# ARM_board.net
KiCad netlist of a schematic drawn in EAGLE
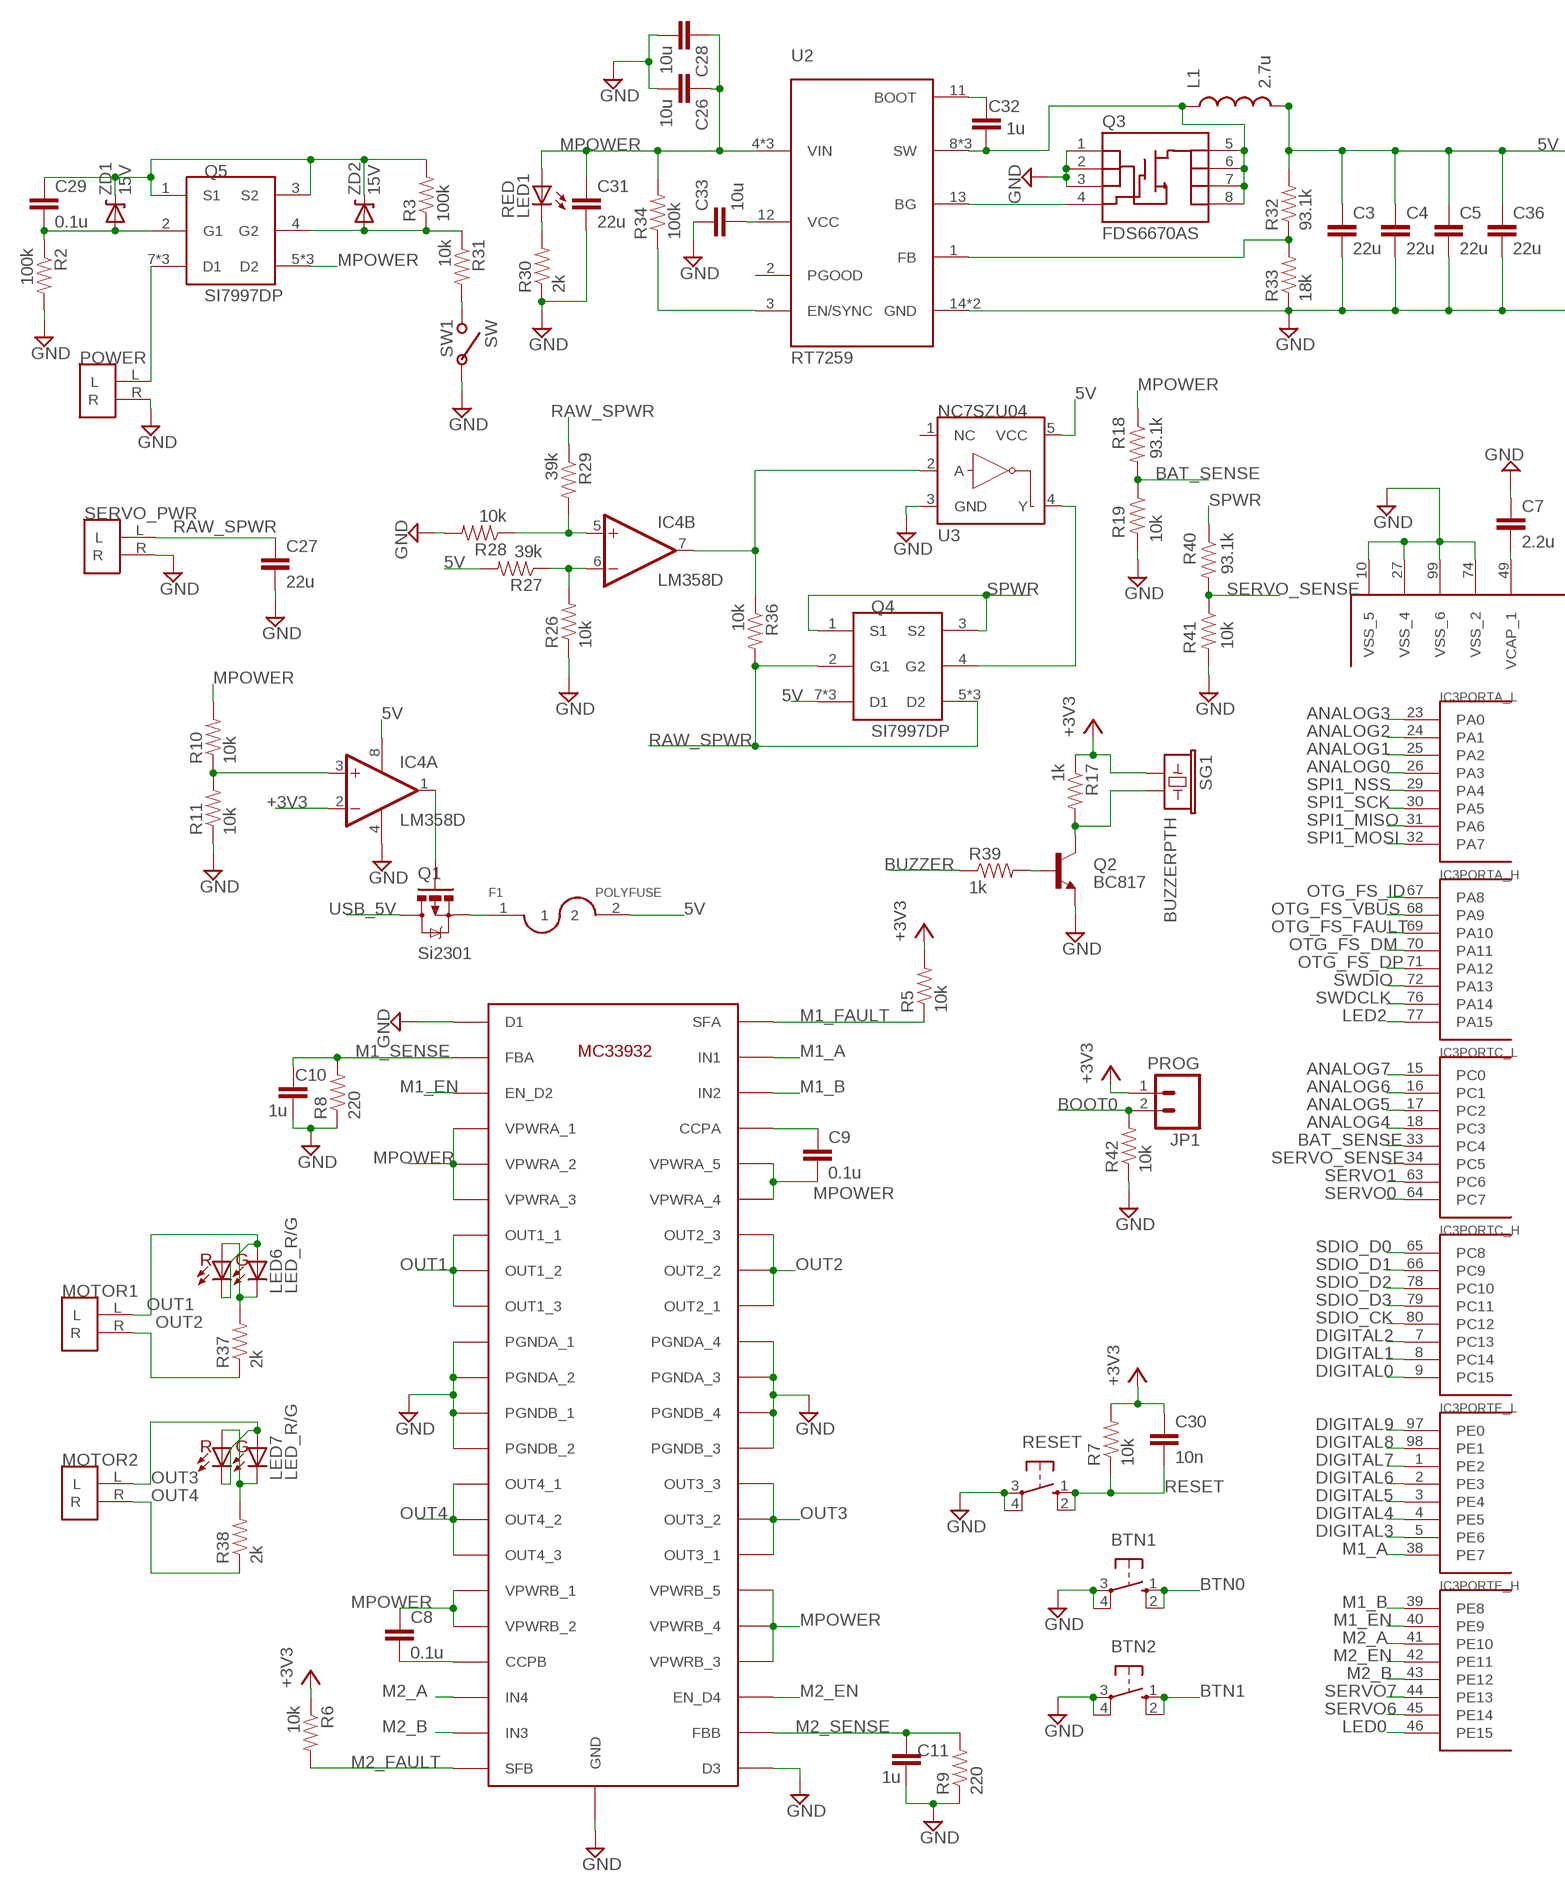
[diagram p0: schematic, sheet 1, part 1 of 2]
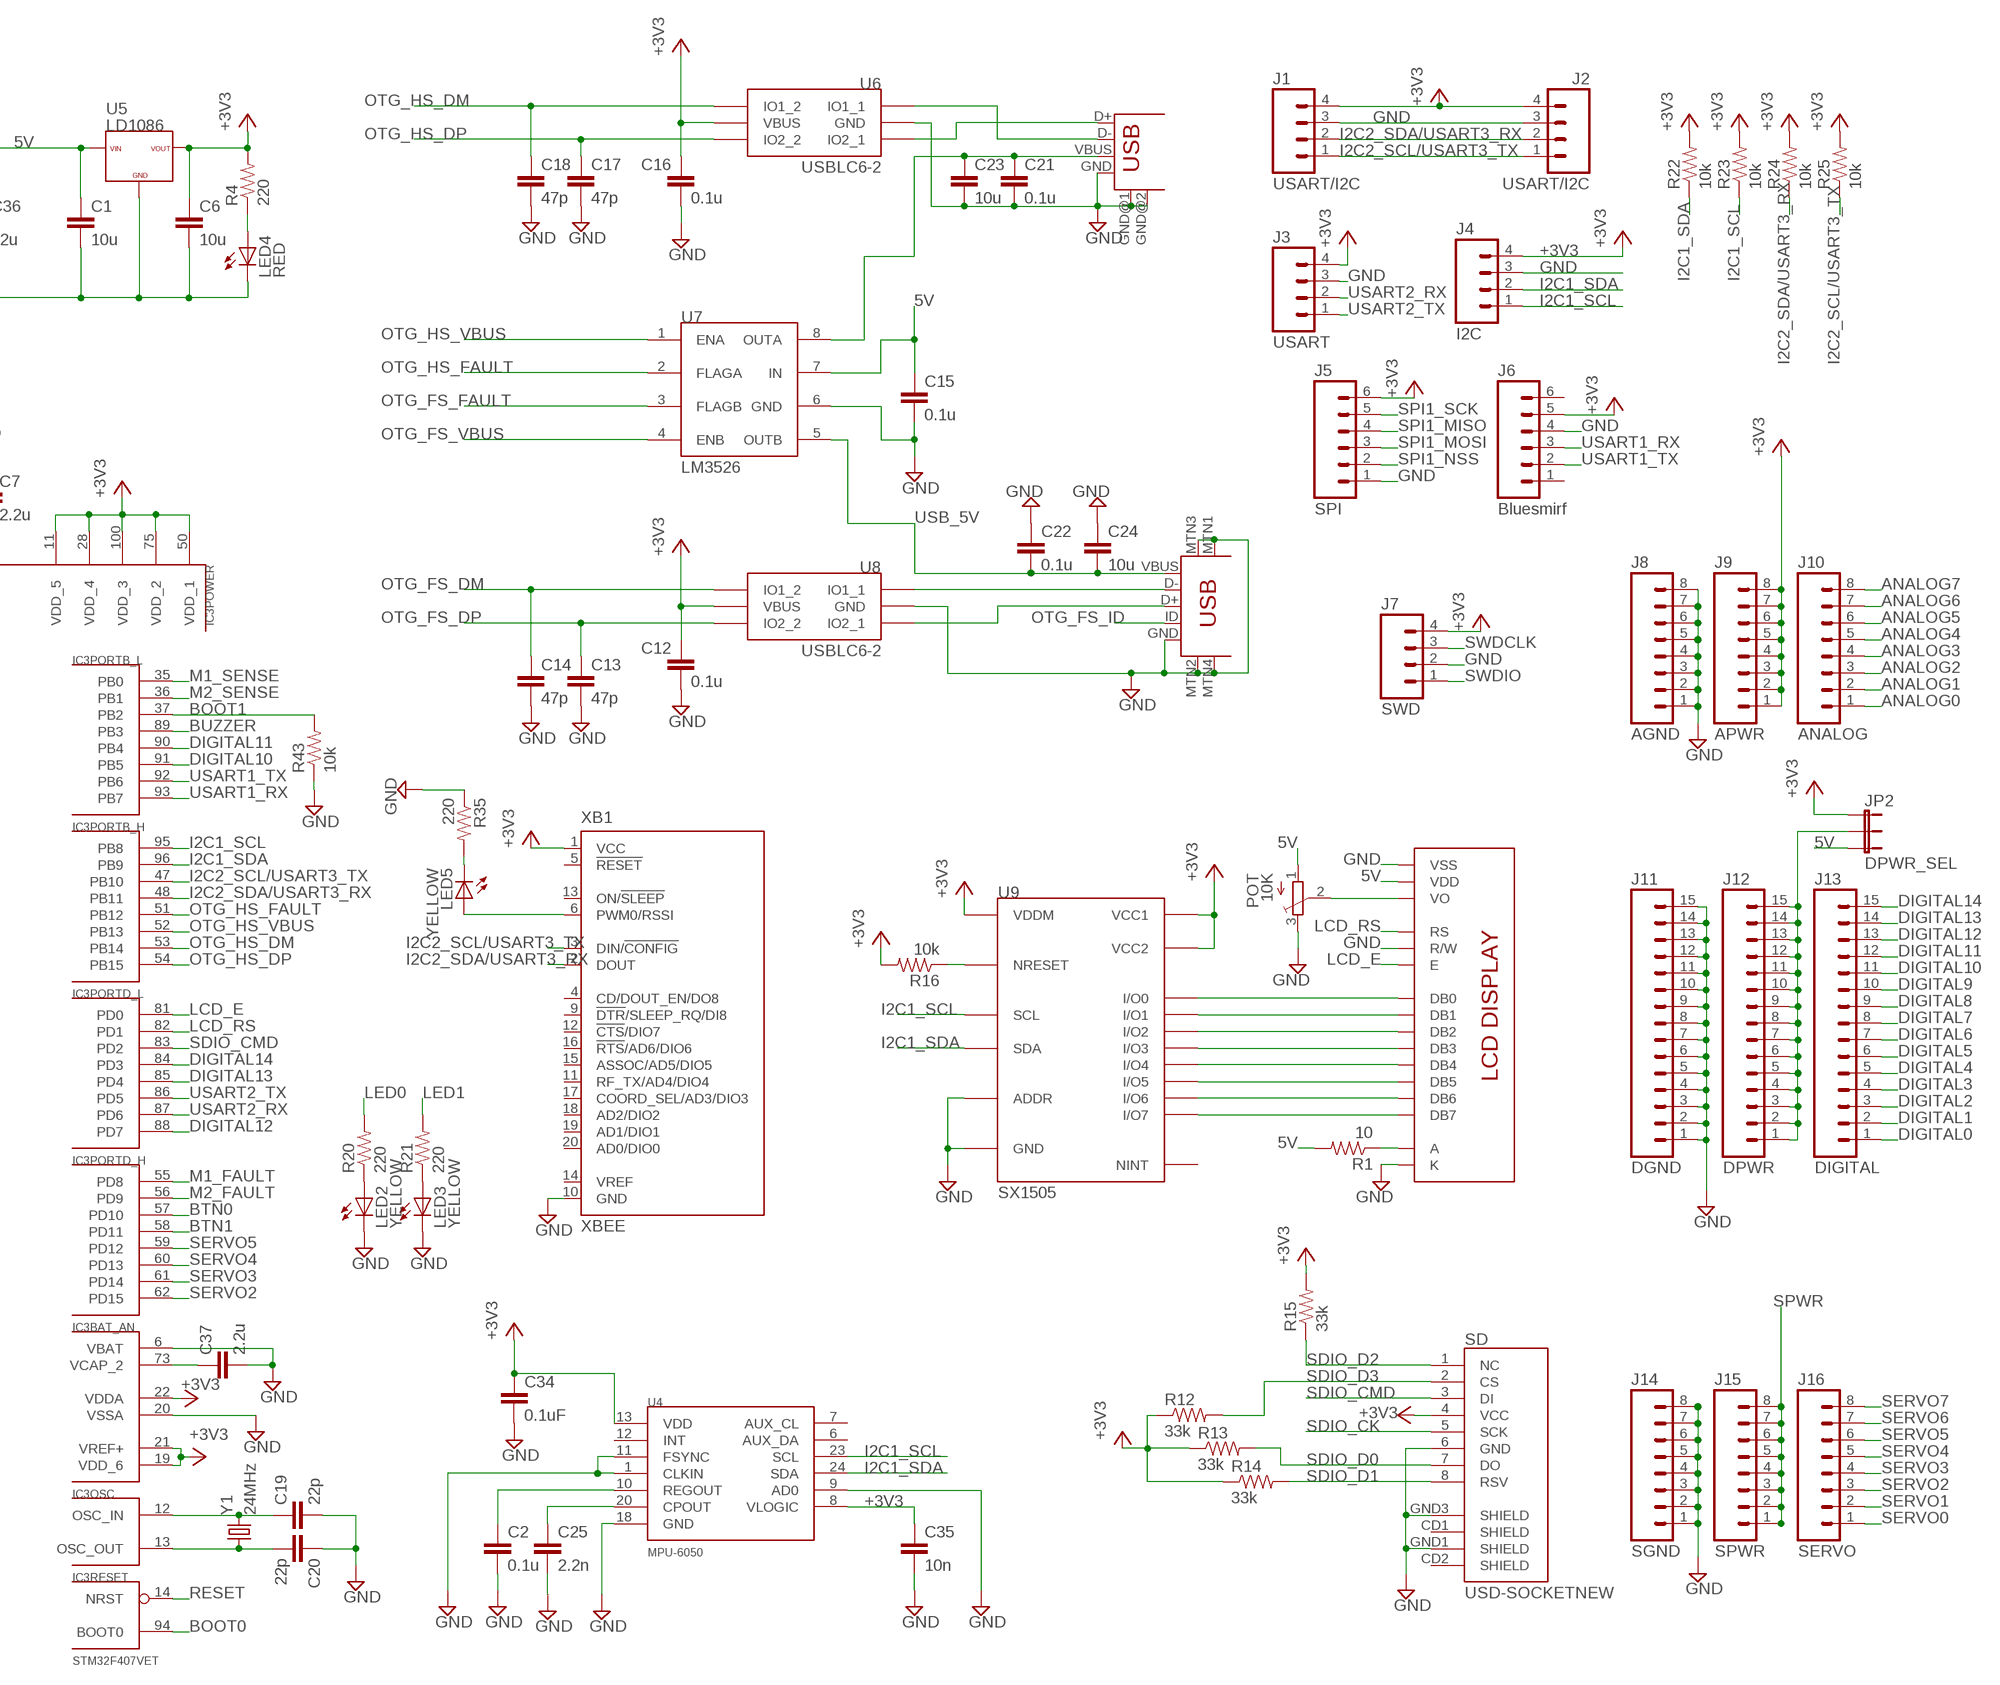
[diagram p1: schematic, sheet 1, part 2 of 2]

(export (version "E")
  (design (tool "Eeschema 10.0.6"))
  (components
    (comp (ref "BTN1")
      (value "10-XX")
      (footprint "eagle-import:B3F-10XX")
      (fields (field (name "MPN") "B3F-1000"))
      (libsource (lib "eagle-import") (part "10-XX"))
    )
    (comp (ref "BTN2")
      (value "10-XX")
      (footprint "eagle-import:B3F-10XX")
      (fields (field (name "MPN") "B3F-1000"))
      (libsource (lib "eagle-import") (part "10-XX"))
    )
    (comp (ref "C1")
      (value "10u")
      (footprint "eagle-import:0805")
      (libsource (lib "eagle-import") (part "CAP0805"))
    )
    (comp (ref "C2")
      (value "0.1u")
      (footprint "eagle-import:0603-CAP")
      (libsource (lib "eagle-import") (part "CAP0603-CAP"))
    )
    (comp (ref "C3")
      (value "22u")
      (footprint "eagle-import:0805")
      (libsource (lib "eagle-import") (part "CAP0805"))
    )
    (comp (ref "C4")
      (value "22u")
      (footprint "eagle-import:0805")
      (libsource (lib "eagle-import") (part "CAP0805"))
    )
    (comp (ref "C5")
      (value "22u")
      (footprint "eagle-import:0805")
      (libsource (lib "eagle-import") (part "CAP0805"))
    )
    (comp (ref "C6")
      (value "10u")
      (footprint "eagle-import:0805")
      (libsource (lib "eagle-import") (part "CAP0805"))
    )
    (comp (ref "C7")
      (value "2.2u")
      (footprint "eagle-import:0603-CAP")
      (libsource (lib "eagle-import") (part "CAP0603-CAP"))
    )
    (comp (ref "C8")
      (value "0.1u")
      (footprint "eagle-import:0603-CAP")
      (libsource (lib "eagle-import") (part "CAP0603-CAP"))
    )
    (comp (ref "C9")
      (value "0.1u")
      (footprint "eagle-import:0603-CAP")
      (libsource (lib "eagle-import") (part "CAP0603-CAP"))
    )
    (comp (ref "C10")
      (value "1u")
      (footprint "eagle-import:0603-CAP")
      (libsource (lib "eagle-import") (part "CAP0603-CAP"))
    )
    (comp (ref "C11")
      (value "1u")
      (footprint "eagle-import:0603-CAP")
      (libsource (lib "eagle-import") (part "CAP0603-CAP"))
    )
    (comp (ref "C12")
      (value "0.1u")
      (footprint "eagle-import:0603-CAP")
      (libsource (lib "eagle-import") (part "CAP0603-CAP"))
    )
    (comp (ref "C13")
      (value "47p")
      (footprint "eagle-import:0603-CAP")
      (libsource (lib "eagle-import") (part "CAP0603-CAP"))
    )
    (comp (ref "C14")
      (value "47p")
      (footprint "eagle-import:0603-CAP")
      (libsource (lib "eagle-import") (part "CAP0603-CAP"))
    )
    (comp (ref "C15")
      (value "0.1u")
      (footprint "eagle-import:0603-CAP")
      (libsource (lib "eagle-import") (part "CAP0603-CAP"))
    )
    (comp (ref "C16")
      (value "0.1u")
      (footprint "eagle-import:0603-CAP")
      (libsource (lib "eagle-import") (part "CAP0603-CAP"))
    )
    (comp (ref "C17")
      (value "47p")
      (footprint "eagle-import:0603-CAP")
      (libsource (lib "eagle-import") (part "CAP0603-CAP"))
    )
    (comp (ref "C18")
      (value "47p")
      (footprint "eagle-import:0603-CAP")
      (libsource (lib "eagle-import") (part "CAP0603-CAP"))
    )
    (comp (ref "C19")
      (value "22p")
      (footprint "eagle-import:0603-CAP")
      (libsource (lib "eagle-import") (part "CAP0603-CAP"))
    )
    (comp (ref "C20")
      (value "22p")
      (footprint "eagle-import:0603-CAP")
      (libsource (lib "eagle-import") (part "CAP0603-CAP"))
    )
    (comp (ref "C21")
      (value "0.1u")
      (footprint "eagle-import:0603-CAP")
      (libsource (lib "eagle-import") (part "CAP0603-CAP"))
    )
    (comp (ref "C22")
      (value "0.1u")
      (footprint "eagle-import:0603-CAP")
      (libsource (lib "eagle-import") (part "CAP0603-CAP"))
    )
    (comp (ref "C23")
      (value "10u")
      (footprint "eagle-import:0805")
      (libsource (lib "eagle-import") (part "CAP0805"))
    )
    (comp (ref "C24")
      (value "10u")
      (footprint "eagle-import:0805")
      (libsource (lib "eagle-import") (part "CAP0805"))
    )
    (comp (ref "C25")
      (value "2.2n")
      (footprint "eagle-import:0603-CAP")
      (libsource (lib "eagle-import") (part "CAP0603-CAP"))
    )
    (comp (ref "C26")
      (value "10u")
      (footprint "eagle-import:1206")
      (libsource (lib "eagle-import") (part "CAP1206"))
    )
    (comp (ref "C27")
      (value "22u")
      (footprint "eagle-import:1206")
      (libsource (lib "eagle-import") (part "CAP1206"))
    )
    (comp (ref "C28")
      (value "10u")
      (footprint "eagle-import:1206")
      (libsource (lib "eagle-import") (part "CAP1206"))
    )
    (comp (ref "C29")
      (value "0.1u")
      (footprint "eagle-import:0603-CAP")
      (libsource (lib "eagle-import") (part "CAP0603-CAP"))
    )
    (comp (ref "C30")
      (value "10n")
      (footprint "eagle-import:0603-CAP")
      (libsource (lib "eagle-import") (part "CAP0603-CAP"))
    )
    (comp (ref "C31")
      (value "22u")
      (footprint "eagle-import:1206")
      (libsource (lib "eagle-import") (part "CAP1206"))
    )
    (comp (ref "C32")
      (value "1u")
      (footprint "eagle-import:0603-CAP")
      (libsource (lib "eagle-import") (part "CAP0603-CAP"))
    )
    (comp (ref "C33")
      (value "10u")
      (footprint "eagle-import:0805")
      (libsource (lib "eagle-import") (part "CAP0805"))
    )
    (comp (ref "C34")
      (value "0.1uF")
      (footprint "eagle-import:0603-CAP")
      (libsource (lib "eagle-import") (part "CAP0603-CAP"))
    )
    (comp (ref "C35")
      (value "10n")
      (footprint "eagle-import:0603-CAP")
      (libsource (lib "eagle-import") (part "CAP0603-CAP"))
    )
    (comp (ref "C36")
      (value "22u")
      (footprint "eagle-import:0805")
      (libsource (lib "eagle-import") (part "CAP0805"))
    )
    (comp (ref "C37")
      (value "2.2u")
      (footprint "eagle-import:0603-CAP")
      (libsource (lib "eagle-import") (part "CAP0603-CAP"))
    )
    (comp (ref "F1")
      (value "POLYFUSE")
      (footprint "eagle-import:1206")
      (libsource (lib "eagle-import") (part "POLYFUSE"))
    )
    (comp (ref "IC3")
      (value "STM32F407VET")
      (footprint "eagle-import:TQFP100")
      (libsource (lib "eagle-import") (part "STM32F407VET"))
    )
    (comp (ref "IC4")
      (value "LM358D")
      (footprint "eagle-import:SO08")
      (libsource (lib "eagle-import") (part "LM358D"))
    )
    (comp (ref "J1")
      (value "USART/I2C")
      (footprint "eagle-import:1X04")
      (libsource (lib "eagle-import") (part "M04PTH"))
    )
    (comp (ref "J2")
      (value "USART/I2C")
      (footprint "eagle-import:1X04")
      (libsource (lib "eagle-import") (part "M04PTH"))
    )
    (comp (ref "J3")
      (value "USART")
      (footprint "eagle-import:1X04")
      (libsource (lib "eagle-import") (part "M04PTH"))
    )
    (comp (ref "J4")
      (value "I2C")
      (footprint "eagle-import:1X04")
      (libsource (lib "eagle-import") (part "M04PTH"))
    )
    (comp (ref "J5")
      (value "SPI")
      (footprint "eagle-import:1X06")
      (libsource (lib "eagle-import") (part "M06SIP"))
    )
    (comp (ref "J6")
      (value "Bluesmirf")
      (footprint "eagle-import:1X06")
      (libsource (lib "eagle-import") (part "M06SIP"))
    )
    (comp (ref "J7")
      (value "SWD")
      (footprint "eagle-import:1X04")
      (libsource (lib "eagle-import") (part "M04PTH"))
    )
    (comp (ref "J8")
      (value "AGND")
      (footprint "eagle-import:1X08")
      (libsource (lib "eagle-import") (part "M081X08"))
    )
    (comp (ref "J9")
      (value "APWR")
      (footprint "eagle-import:1X08")
      (libsource (lib "eagle-import") (part "M081X08"))
    )
    (comp (ref "J10")
      (value "ANALOG")
      (footprint "eagle-import:1X08")
      (libsource (lib "eagle-import") (part "M081X08"))
    )
    (comp (ref "J11")
      (value "DGND")
      (footprint "eagle-import:1X15")
      (libsource (lib "eagle-import") (part "M15"))
    )
    (comp (ref "J12")
      (value "DPWR")
      (footprint "eagle-import:1X15")
      (libsource (lib "eagle-import") (part "M15"))
    )
    (comp (ref "J13")
      (value "DIGITAL")
      (footprint "eagle-import:1X15")
      (libsource (lib "eagle-import") (part "M15"))
    )
    (comp (ref "J14")
      (value "SGND")
      (footprint "eagle-import:1X08")
      (libsource (lib "eagle-import") (part "M081X08"))
    )
    (comp (ref "J15")
      (value "SPWR")
      (footprint "eagle-import:1X08")
      (libsource (lib "eagle-import") (part "M081X08"))
    )
    (comp (ref "J16")
      (value "SERVO")
      (footprint "eagle-import:1X08")
      (libsource (lib "eagle-import") (part "M081X08"))
    )
    (comp (ref "JP1")
      (value "PROG")
      (footprint "eagle-import:1X02")
      (libsource (lib "eagle-import") (part "M02PTH"))
    )
    (comp (ref "JP2")
      (value "DPWR_SEL")
      (footprint "eagle-import:1X03")
      (libsource (lib "eagle-import") (part "JUMPER-3PTH"))
    )
    (comp (ref "L1")
      (value "2.7u")
      (footprint "eagle-import:INDUCTOR")
      (libsource (lib "eagle-import") (part "INDUCTOR"))
    )
    (comp (ref "LCD")
      (value "LCD_DISPLAY")
      (footprint "eagle-import:LCD")
      (libsource (lib "eagle-import") (part "LCD_DISPLAY"))
    )
    (comp (ref "LED1")
      (value "RED")
      (footprint "eagle-import:CHIP-LED0603")
      (libsource (lib "eagle-import") (part "LEDCHIP-LED0603"))
    )
    (comp (ref "LED2")
      (value "YELLOW")
      (footprint "eagle-import:CHIP-LED0603")
      (libsource (lib "eagle-import") (part "LEDCHIP-LED0603"))
    )
    (comp (ref "LED3")
      (value "YELLOW")
      (footprint "eagle-import:CHIP-LED0603")
      (libsource (lib "eagle-import") (part "LEDCHIP-LED0603"))
    )
    (comp (ref "LED4")
      (value "RED")
      (footprint "eagle-import:CHIP-LED0603")
      (libsource (lib "eagle-import") (part "LEDCHIP-LED0603"))
    )
    (comp (ref "LED5")
      (value "YELLOW")
      (footprint "eagle-import:CHIP-LED0603")
      (libsource (lib "eagle-import") (part "LEDCHIP-LED0603"))
    )
    (comp (ref "LED6")
      (value "LED_R/G")
      (footprint "eagle-import:LED-0606")
      (libsource (lib "eagle-import") (part "LED_BICOLOR"))
    )
    (comp (ref "LED7")
      (value "LED_R/G")
      (footprint "eagle-import:LED-0606")
      (libsource (lib "eagle-import") (part "LED_BICOLOR"))
    )
    (comp (ref "MOTOR1")
      (value "2POS_TERMINAL")
      (footprint "eagle-import:2POS_TERMINAL")
      (libsource (lib "eagle-import") (part "2POS_TERMINAL"))
    )
    (comp (ref "MOTOR2")
      (value "2POS_TERMINAL")
      (footprint "eagle-import:2POS_TERMINAL")
      (libsource (lib "eagle-import") (part "2POS_TERMINAL"))
    )
    (comp (ref "POT")
      (value "10K")
      (footprint "eagle-import:POT")
      (libsource (lib "eagle-import") (part "POT"))
    )
    (comp (ref "POWER")
      (value "2POS_TERMINAL")
      (footprint "eagle-import:2POS_TERMINAL")
      (libsource (lib "eagle-import") (part "2POS_TERMINAL"))
    )
    (comp (ref "Q1")
      (value "Si2301")
      (footprint "eagle-import:SOT23-3")
      (libsource (lib "eagle-import") (part "MOSFET-PCHANNELSMD"))
    )
    (comp (ref "Q2")
      (value "BC817")
      (footprint "eagle-import:SOT23-3")
      (libsource (lib "eagle-import") (part "TRANSISTOR_NPNSOT23-3"))
    )
    (comp (ref "Q3")
      (value "FDS6670AS")
      (footprint "eagle-import:SO08")
      (libsource (lib "eagle-import") (part "MOSFET-NCHANNEL-SOIC8"))
    )
    (comp (ref "Q4")
      (value "SI7997DP")
      (footprint "eagle-import:POWERPAK")
      (libsource (lib "eagle-import") (part "SI7997DP"))
    )
    (comp (ref "Q5")
      (value "SI7997DP")
      (footprint "eagle-import:POWERPAK")
      (libsource (lib "eagle-import") (part "SI7997DP"))
    )
    (comp (ref "R1")
      (value "10")
      (footprint "eagle-import:0603-RES")
      (libsource (lib "eagle-import") (part "RESISTOR0603-RES"))
    )
    (comp (ref "R2")
      (value "100k")
      (footprint "eagle-import:0603-RES")
      (libsource (lib "eagle-import") (part "RESISTOR0603-RES"))
    )
    (comp (ref "R3")
      (value "100k")
      (footprint "eagle-import:0603-RES")
      (libsource (lib "eagle-import") (part "RESISTOR0603-RES"))
    )
    (comp (ref "R4")
      (value "220")
      (footprint "eagle-import:0603-RES")
      (libsource (lib "eagle-import") (part "RESISTOR0603-RES"))
    )
    (comp (ref "R5")
      (value "10k")
      (footprint "eagle-import:0603-RES")
      (libsource (lib "eagle-import") (part "RESISTOR0603-RES"))
    )
    (comp (ref "R6")
      (value "10k")
      (footprint "eagle-import:0603-RES")
      (libsource (lib "eagle-import") (part "RESISTOR0603-RES"))
    )
    (comp (ref "R7")
      (value "10k")
      (footprint "eagle-import:0603-RES")
      (libsource (lib "eagle-import") (part "RESISTOR0603-RES"))
    )
    (comp (ref "R8")
      (value "220")
      (footprint "eagle-import:0603-RES")
      (libsource (lib "eagle-import") (part "RESISTOR0603-RES"))
    )
    (comp (ref "R9")
      (value "220")
      (footprint "eagle-import:0603-RES")
      (libsource (lib "eagle-import") (part "RESISTOR0603-RES"))
    )
    (comp (ref "R10")
      (value "10k")
      (footprint "eagle-import:0603-RES")
      (libsource (lib "eagle-import") (part "RESISTOR0603-RES"))
    )
    (comp (ref "R11")
      (value "10k")
      (footprint "eagle-import:0603-RES")
      (libsource (lib "eagle-import") (part "RESISTOR0603-RES"))
    )
    (comp (ref "R12")
      (value "33k")
      (footprint "eagle-import:0603-RES")
      (libsource (lib "eagle-import") (part "RESISTOR0603-RES"))
    )
    (comp (ref "R13")
      (value "33k")
      (footprint "eagle-import:0603-RES")
      (libsource (lib "eagle-import") (part "RESISTOR0603-RES"))
    )
    (comp (ref "R14")
      (value "33k")
      (footprint "eagle-import:0603-RES")
      (libsource (lib "eagle-import") (part "RESISTOR0603-RES"))
    )
    (comp (ref "R15")
      (value "33k")
      (footprint "eagle-import:0603-RES")
      (libsource (lib "eagle-import") (part "RESISTOR0603-RES"))
    )
    (comp (ref "R16")
      (value "10k")
      (footprint "eagle-import:0603-RES")
      (libsource (lib "eagle-import") (part "RESISTOR0603-RES"))
    )
    (comp (ref "R17")
      (value "1k")
      (footprint "eagle-import:0603-RES")
      (libsource (lib "eagle-import") (part "RESISTOR0603-RES"))
    )
    (comp (ref "R18")
      (value "93.1k")
      (footprint "eagle-import:0603-RES")
      (libsource (lib "eagle-import") (part "RESISTOR0603-RES"))
    )
    (comp (ref "R19")
      (value "10k")
      (footprint "eagle-import:0603-RES")
      (libsource (lib "eagle-import") (part "RESISTOR0603-RES"))
    )
    (comp (ref "R20")
      (value "220")
      (footprint "eagle-import:0603-RES")
      (libsource (lib "eagle-import") (part "RESISTOR0603-RES"))
    )
    (comp (ref "R21")
      (value "220")
      (footprint "eagle-import:0603-RES")
      (libsource (lib "eagle-import") (part "RESISTOR0603-RES"))
    )
    (comp (ref "R22")
      (value "10k")
      (footprint "eagle-import:0603-RES")
      (libsource (lib "eagle-import") (part "RESISTOR0603-RES"))
    )
    (comp (ref "R23")
      (value "10k")
      (footprint "eagle-import:0603-RES")
      (libsource (lib "eagle-import") (part "RESISTOR0603-RES"))
    )
    (comp (ref "R24")
      (value "10k")
      (footprint "eagle-import:0603-RES")
      (libsource (lib "eagle-import") (part "RESISTOR0603-RES"))
    )
    (comp (ref "R25")
      (value "10k")
      (footprint "eagle-import:0603-RES")
      (libsource (lib "eagle-import") (part "RESISTOR0603-RES"))
    )
    (comp (ref "R26")
      (value "10k")
      (footprint "eagle-import:0603-RES")
      (libsource (lib "eagle-import") (part "RESISTOR0603-RES"))
    )
    (comp (ref "R27")
      (value "39k")
      (footprint "eagle-import:0603-RES")
      (libsource (lib "eagle-import") (part "RESISTOR0603-RES"))
    )
    (comp (ref "R28")
      (value "10k")
      (footprint "eagle-import:0603-RES")
      (libsource (lib "eagle-import") (part "RESISTOR0603-RES"))
    )
    (comp (ref "R29")
      (value "39k")
      (footprint "eagle-import:0603-RES")
      (libsource (lib "eagle-import") (part "RESISTOR0603-RES"))
    )
    (comp (ref "R30")
      (value "2k")
      (footprint "eagle-import:0603-RES")
      (libsource (lib "eagle-import") (part "RESISTOR0603-RES"))
    )
    (comp (ref "R31")
      (value "10k")
      (footprint "eagle-import:0603-RES")
      (libsource (lib "eagle-import") (part "RESISTOR0603-RES"))
    )
    (comp (ref "R32")
      (value "93.1k")
      (footprint "eagle-import:0603-RES")
      (libsource (lib "eagle-import") (part "RESISTOR0603-RES"))
    )
    (comp (ref "R33")
      (value "18k")
      (footprint "eagle-import:0603-RES")
      (libsource (lib "eagle-import") (part "RESISTOR0603-RES"))
    )
    (comp (ref "R34")
      (value "100k")
      (footprint "eagle-import:0603-RES")
      (libsource (lib "eagle-import") (part "RESISTOR0603-RES"))
    )
    (comp (ref "R35")
      (value "220")
      (footprint "eagle-import:0603-RES")
      (libsource (lib "eagle-import") (part "RESISTOR0603-RES"))
    )
    (comp (ref "R36")
      (value "10k")
      (footprint "eagle-import:0603-RES")
      (libsource (lib "eagle-import") (part "RESISTOR0603-RES"))
    )
    (comp (ref "R37")
      (value "2k")
      (footprint "eagle-import:0603-RES")
      (libsource (lib "eagle-import") (part "RESISTOR0603-RES"))
    )
    (comp (ref "R38")
      (value "2k")
      (footprint "eagle-import:0603-RES")
      (libsource (lib "eagle-import") (part "RESISTOR0603-RES"))
    )
    (comp (ref "R39")
      (value "1k")
      (footprint "eagle-import:0603-RES")
      (libsource (lib "eagle-import") (part "RESISTOR0603-RES"))
    )
    (comp (ref "R40")
      (value "93.1k")
      (footprint "eagle-import:0603-RES")
      (libsource (lib "eagle-import") (part "RESISTOR0603-RES"))
    )
    (comp (ref "R41")
      (value "10k")
      (footprint "eagle-import:0603-RES")
      (libsource (lib "eagle-import") (part "RESISTOR0603-RES"))
    )
    (comp (ref "R42")
      (value "10k")
      (footprint "eagle-import:0603-RES")
      (libsource (lib "eagle-import") (part "RESISTOR0603-RES"))
    )
    (comp (ref "R43")
      (value "10k")
      (footprint "eagle-import:0603-RES")
      (libsource (lib "eagle-import") (part "RESISTOR0603-RES"))
    )
    (comp (ref "RESET")
      (value "10-XX")
      (footprint "eagle-import:B3F-10XX")
      (fields (field (name "MPN") "B3F-1000"))
      (libsource (lib "eagle-import") (part "10-XX"))
    )
    (comp (ref "SD")
      (value "USD-SOCKETNEW")
      (footprint "eagle-import:MICRO-SD-SOCKET-PP")
      (libsource (lib "eagle-import") (part "USD-SOCKETNEW"))
    )
    (comp (ref "SERVO_PWR")
      (value "2POS_TERMINAL")
      (footprint "eagle-import:2POS_TERMINAL")
      (libsource (lib "eagle-import") (part "2POS_TERMINAL"))
    )
    (comp (ref "SG1")
      (value "BUZZERPTH")
      (footprint "eagle-import:BUZZER-12MM")
      (libsource (lib "eagle-import") (part "BUZZERPTH"))
    )
    (comp (ref "SW1") (value "SW") (footprint "eagle-import:SW") (libsource (lib "eagle-import") (part "SW")))
    (comp (ref "U1")
      (value "MC33932")
      (footprint "eagle-import:HSOP44")
      (libsource (lib "eagle-import") (part "MC33932"))
    )
    (comp (ref "U2")
      (value "RT7259")
      (footprint "eagle-import:WDFN-14L")
      (libsource (lib "eagle-import") (part "SWITCHING_REG"))
    )
    (comp (ref "U3")
      (value "NC7SZU04")
      (footprint "eagle-import:SC70")
      (libsource (lib "eagle-import") (part "INVERTER{dblquote}{dblquote}"))
    )
    (comp (ref "U4")
      (value "MPU-6050")
      (footprint "eagle-import:QFN-24_IMU")
      (libsource (lib "eagle-import") (part "MPU-6050"))
    )
    (comp (ref "U5")
      (value "LD1086")
      (footprint "eagle-import:D2PAK")
      (libsource (lib "eagle-import") (part "LD1086"))
    )
    (comp (ref "U6")
      (value "USBLC6-2")
      (footprint "eagle-import:SOT23-6L")
      (libsource (lib "eagle-import") (part "USBLC6-2"))
    )
    (comp (ref "U7")
      (value "LM3526")
      (footprint "eagle-import:SO08")
      (libsource (lib "eagle-import") (part "LM3526"))
    )
    (comp (ref "U8")
      (value "USBLC6-2")
      (footprint "eagle-import:SOT23-6L")
      (libsource (lib "eagle-import") (part "USBLC6-2"))
    )
    (comp (ref "U9")
      (value "SX1505")
      (footprint "eagle-import:QFN-UT-20")
      (libsource (lib "eagle-import") (part "I2C_EXPANDER"))
    )
    (comp (ref "USB1")
      (value "USB-A-S")
      (footprint "eagle-import:USB-A-S")
      (libsource (lib "eagle-import") (part "USB-A-S"))
    )
    (comp (ref "USB2")
      (value "USB-MINIB-5PIN")
      (footprint "eagle-import:USB-MINIB")
      (libsource (lib "eagle-import") (part "USB-MINIB-5PIN"))
    )
    (comp (ref "XB1")
      (value "XBEE")
      (footprint "eagle-import:XBEE")
      (fields
        (field (name "MPN") "XBP24-Z7UIT-004")
        (field (name "MPN_1") "XBP24-Z7UIT-004")
        (field (name "OC_FARNELL") "1751799")
        (field (name "OC_NEWARK") "34R5507")
      )
      (libsource (lib "eagle-import") (part "XBEE"))
    )
    (comp (ref "Y1")
      (value "24MHz")
      (footprint "eagle-import:HC49UP")
      (libsource (lib "eagle-import") (part "CRYSTALSMD"))
    )
    (comp (ref "ZD1")
      (value "15V")
      (footprint "eagle-import:0603")
      (libsource (lib "eagle-import") (part "ZENER"))
    )
    (comp (ref "ZD2")
      (value "15V")
      (footprint "eagle-import:0603")
      (libsource (lib "eagle-import") (part "ZENER"))
    )
  )
  (nets
    (net (code "1") (name "+3V3") (class "Default")
      (node (ref "C12") (pin "1") (pinfunction "1_1") (pintype "passive"))
      (node (ref "C16") (pin "1") (pinfunction "1_1") (pintype "passive"))
      (node (ref "C30") (pin "1") (pinfunction "1_1") (pintype "passive"))
      (node (ref "C34") (pin "1") (pinfunction "1_1") (pintype "passive"))
      (node (ref "C35") (pin "1") (pinfunction "1_1") (pintype "passive"))
      (node (ref "C6") (pin "1") (pinfunction "1_1") (pintype "passive"))
      (node (ref "IC3") (pin "100") (pinfunction "VDD_3_100") (pintype "power_in"))
      (node (ref "IC3") (pin "11") (pinfunction "VDD_5_11") (pintype "power_in"))
      (node (ref "IC3") (pin "19") (pinfunction "VDD_6_19") (pintype "input"))
      (node (ref "IC3") (pin "21") (pinfunction "VREF+_21") (pintype "input"))
      (node (ref "IC3") (pin "22") (pinfunction "VDDA_22") (pintype "power_in"))
      (node (ref "IC3") (pin "28") (pinfunction "VDD_4_28") (pintype "power_in"))
      (node (ref "IC3") (pin "50") (pinfunction "VDD_1_50") (pintype "power_in"))
      (node (ref "IC3") (pin "75") (pinfunction "VDD_2_75") (pintype "power_in"))
      (node (ref "IC4") (pin "2") (pinfunction "-IN_2") (pintype "input"))
      (node (ref "J1") (pin "4") (pinfunction "4_4") (pintype "passive"))
      (node (ref "J2") (pin "4") (pinfunction "4_4") (pintype "passive"))
      (node (ref "J3") (pin "4") (pinfunction "4_4") (pintype "passive"))
      (node (ref "J4") (pin "4") (pinfunction "4_4") (pintype "passive"))
      (node (ref "J5") (pin "6") (pinfunction "6_6") (pintype "passive"))
      (node (ref "J6") (pin "5") (pinfunction "5_5") (pintype "passive"))
      (node (ref "J7") (pin "4") (pinfunction "4_4") (pintype "passive"))
      (node (ref "J9") (pin "1") (pinfunction "1_1") (pintype "passive"))
      (node (ref "J9") (pin "2") (pinfunction "2_2") (pintype "passive"))
      (node (ref "J9") (pin "3") (pinfunction "3_3") (pintype "passive"))
      (node (ref "J9") (pin "4") (pinfunction "4_4") (pintype "passive"))
      (node (ref "J9") (pin "5") (pinfunction "5_5") (pintype "passive"))
      (node (ref "J9") (pin "6") (pinfunction "6_6") (pintype "passive"))
      (node (ref "J9") (pin "7") (pinfunction "7_7") (pintype "passive"))
      (node (ref "J9") (pin "8") (pinfunction "8_8") (pintype "passive"))
      (node (ref "JP1") (pin "1") (pinfunction "1_1") (pintype "passive"))
      (node (ref "JP2") (pin "1") (pinfunction "1_1") (pintype "passive"))
      (node (ref "R12") (pin "1") (pinfunction "1_1") (pintype "passive"))
      (node (ref "R13") (pin "1") (pinfunction "1_1") (pintype "passive"))
      (node (ref "R14") (pin "1") (pinfunction "1_1") (pintype "passive"))
      (node (ref "R15") (pin "2") (pinfunction "2_2") (pintype "passive"))
      (node (ref "R16") (pin "2") (pinfunction "2_2") (pintype "passive"))
      (node (ref "R17") (pin "1") (pinfunction "1_1") (pintype "passive"))
      (node (ref "R22") (pin "2") (pinfunction "2_2") (pintype "passive"))
      (node (ref "R23") (pin "2") (pinfunction "2_2") (pintype "passive"))
      (node (ref "R24") (pin "2") (pinfunction "2_2") (pintype "passive"))
      (node (ref "R25") (pin "2") (pinfunction "2_2") (pintype "passive"))
      (node (ref "R4") (pin "2") (pinfunction "2_2") (pintype "passive"))
      (node (ref "R5") (pin "2") (pinfunction "2_2") (pintype "passive"))
      (node (ref "R6") (pin "1") (pinfunction "1_1") (pintype "passive"))
      (node (ref "R7") (pin "2") (pinfunction "2_2") (pintype "passive"))
      (node (ref "SD") (pin "4") (pinfunction "VCC_4") (pintype "bidirectional"))
      (node (ref "SG1") (pin "+") (pinfunction "1_+") (pintype "passive"))
      (node (ref "U4") (pin "13") (pinfunction "VDD_13") (pintype "bidirectional"))
      (node (ref "U4") (pin "8") (pinfunction "VLOGIC_8") (pintype "bidirectional"))
      (node (ref "U5") (pin "VOUT") (pinfunction "VOUT_VOUT") (pintype "bidirectional"))
      (node (ref "U6") (pin "P$5") (pinfunction "VBUS_P$5") (pintype "bidirectional"))
      (node (ref "U8") (pin "P$5") (pinfunction "VBUS_P$5") (pintype "bidirectional"))
      (node (ref "U9") (pin "P$14") (pinfunction "VDDM_P$14") (pintype "bidirectional"))
      (node (ref "U9") (pin "P$17") (pinfunction "VCC2_P$17") (pintype "bidirectional"))
      (node (ref "U9") (pin "P$7") (pinfunction "VCC1_P$7") (pintype "bidirectional"))
      (node (ref "XB1") (pin "1") (pinfunction "VCC_1") (pintype "power_in"))
    )
    (net (code "2") (name "/5V") (class "Default")
      (node (ref "C1") (pin "1") (pinfunction "1_1") (pintype "passive"))
      (node (ref "C15") (pin "1") (pinfunction "1_1") (pintype "passive"))
      (node (ref "C3") (pin "1") (pinfunction "1_1") (pintype "passive"))
      (node (ref "C36") (pin "1") (pinfunction "1_1") (pintype "passive"))
      (node (ref "C4") (pin "1") (pinfunction "1_1") (pintype "passive"))
      (node (ref "C5") (pin "1") (pinfunction "1_1") (pintype "passive"))
      (node (ref "F1") (pin "2") (pinfunction "2_2") (pintype "bidirectional"))
      (node (ref "IC4") (pin "8") (pinfunction "V+_8") (pintype "power_in"))
      (node (ref "JP2") (pin "3") (pinfunction "3_3") (pintype "passive"))
      (node (ref "L1") (pin "P$2") (pinfunction "2_P$2") (pintype "passive"))
      (node (ref "LCD") (pin "VDD") (pinfunction "VDD_VDD") (pintype "bidirectional"))
      (node (ref "POT") (pin "1") (pinfunction "A_1") (pintype "passive"))
      (node (ref "Q4") (pin "7") (pinfunction "D1_7") (pintype "bidirectional"))
      (node (ref "Q4") (pin "8") (pinfunction "D1_8") (pintype "bidirectional"))
      (node (ref "Q4") (pin "9") (pinfunction "D1_9") (pintype "bidirectional"))
      (node (ref "R1") (pin "2") (pinfunction "2_2") (pintype "passive"))
      (node (ref "R27") (pin "2") (pinfunction "2_2") (pintype "passive"))
      (node (ref "R32") (pin "2") (pinfunction "2_2") (pintype "passive"))
      (node (ref "U3") (pin "5") (pinfunction "VCC_5") (pintype "bidirectional"))
      (node (ref "U5") (pin "VIN") (pinfunction "VIN_VIN") (pintype "bidirectional"))
      (node (ref "U7") (pin "7") (pinfunction "IN_7") (pintype "bidirectional"))
    )
    (net (code "3") (name "/ANALOG0") (class "Default")
      (node (ref "IC3") (pin "26") (pinfunction "PA3_26") (pintype "bidirectional"))
      (node (ref "J10") (pin "1") (pinfunction "1_1") (pintype "passive"))
    )
    (net (code "4") (name "/ANALOG1") (class "Default")
      (node (ref "IC3") (pin "25") (pinfunction "PA2_25") (pintype "bidirectional"))
      (node (ref "J10") (pin "2") (pinfunction "2_2") (pintype "passive"))
    )
    (net (code "5") (name "/ANALOG2") (class "Default")
      (node (ref "IC3") (pin "24") (pinfunction "PA1_24") (pintype "bidirectional"))
      (node (ref "J10") (pin "3") (pinfunction "3_3") (pintype "passive"))
    )
    (net (code "6") (name "/ANALOG3") (class "Default")
      (node (ref "IC3") (pin "23") (pinfunction "PA0_23") (pintype "bidirectional"))
      (node (ref "J10") (pin "4") (pinfunction "4_4") (pintype "passive"))
    )
    (net (code "7") (name "/ANALOG4") (class "Default")
      (node (ref "IC3") (pin "18") (pinfunction "PC3_18") (pintype "bidirectional"))
      (node (ref "J10") (pin "5") (pinfunction "5_5") (pintype "passive"))
    )
    (net (code "8") (name "/ANALOG5") (class "Default")
      (node (ref "IC3") (pin "17") (pinfunction "PC2_17") (pintype "bidirectional"))
      (node (ref "J10") (pin "6") (pinfunction "6_6") (pintype "passive"))
    )
    (net (code "9") (name "/ANALOG6") (class "Default")
      (node (ref "IC3") (pin "16") (pinfunction "PC1_16") (pintype "bidirectional"))
      (node (ref "J10") (pin "7") (pinfunction "7_7") (pintype "passive"))
    )
    (net (code "10") (name "/ANALOG7") (class "Default")
      (node (ref "IC3") (pin "15") (pinfunction "PC0_15") (pintype "bidirectional"))
      (node (ref "J10") (pin "8") (pinfunction "8_8") (pintype "passive"))
    )
    (net (code "11") (name "/BAT_SENSE") (class "Default")
      (node (ref "IC3") (pin "33") (pinfunction "PC4_33") (pintype "bidirectional"))
      (node (ref "R18") (pin "2") (pinfunction "2_2") (pintype "passive"))
      (node (ref "R19") (pin "1") (pinfunction "1_1") (pintype "passive"))
    )
    (net (code "12") (name "/BOOT0") (class "Default")
      (node (ref "IC3") (pin "94") (pinfunction "BOOT0_94") (pintype "input"))
      (node (ref "JP1") (pin "2") (pinfunction "2_2") (pintype "passive"))
      (node (ref "R42") (pin "2") (pinfunction "2_2") (pintype "passive"))
    )
    (net (code "13") (name "/BOOT1") (class "Default")
      (node (ref "IC3") (pin "37") (pinfunction "PB2_37") (pintype "bidirectional"))
      (node (ref "R43") (pin "2") (pinfunction "2_2") (pintype "passive"))
    )
    (net (code "14") (name "/BTN0") (class "Default")
      (node (ref "BTN1") (pin "1") (pinfunction "S_1") (pintype "passive"))
      (node (ref "BTN1") (pin "2") (pinfunction "S1_2") (pintype "passive"))
      (node (ref "IC3") (pin "57") (pinfunction "PD10_57") (pintype "bidirectional"))
    )
    (net (code "15") (name "/BTN1") (class "Default")
      (node (ref "BTN2") (pin "1") (pinfunction "S_1") (pintype "passive"))
      (node (ref "BTN2") (pin "2") (pinfunction "S1_2") (pintype "passive"))
      (node (ref "IC3") (pin "58") (pinfunction "PD11_58") (pintype "bidirectional"))
    )
    (net (code "16") (name "/BUZZER") (class "Default")
      (node (ref "IC3") (pin "89") (pinfunction "PB3_89") (pintype "bidirectional"))
      (node (ref "R39") (pin "1") (pinfunction "1_1") (pintype "passive"))
    )
    (net (code "17") (name "/DIGITAL0") (class "Default")
      (node (ref "IC3") (pin "9") (pinfunction "PC15_9") (pintype "bidirectional"))
      (node (ref "J13") (pin "1") (pinfunction "1_1") (pintype "passive"))
    )
    (net (code "18") (name "/DIGITAL1") (class "Default")
      (node (ref "IC3") (pin "8") (pinfunction "PC14_8") (pintype "bidirectional"))
      (node (ref "J13") (pin "2") (pinfunction "2_2") (pintype "passive"))
    )
    (net (code "19") (name "/DIGITAL2") (class "Default")
      (node (ref "IC3") (pin "7") (pinfunction "PC13_7") (pintype "bidirectional"))
      (node (ref "J13") (pin "3") (pinfunction "3_3") (pintype "passive"))
    )
    (net (code "20") (name "/DIGITAL3") (class "Default")
      (node (ref "IC3") (pin "5") (pinfunction "PE6_5") (pintype "bidirectional"))
      (node (ref "J13") (pin "4") (pinfunction "4_4") (pintype "passive"))
    )
    (net (code "21") (name "/DIGITAL4") (class "Default")
      (node (ref "IC3") (pin "4") (pinfunction "PE5_4") (pintype "bidirectional"))
      (node (ref "J13") (pin "5") (pinfunction "5_5") (pintype "passive"))
    )
    (net (code "22") (name "/DIGITAL5") (class "Default")
      (node (ref "IC3") (pin "3") (pinfunction "PE4_3") (pintype "bidirectional"))
      (node (ref "J13") (pin "6") (pinfunction "6_6") (pintype "passive"))
    )
    (net (code "23") (name "/DIGITAL6") (class "Default")
      (node (ref "IC3") (pin "2") (pinfunction "PE3_2") (pintype "bidirectional"))
      (node (ref "J13") (pin "7") (pinfunction "7_7") (pintype "passive"))
    )
    (net (code "24") (name "/DIGITAL7") (class "Default")
      (node (ref "IC3") (pin "1") (pinfunction "PE2_1") (pintype "bidirectional"))
      (node (ref "J13") (pin "8") (pinfunction "8_8") (pintype "passive"))
    )
    (net (code "25") (name "/DIGITAL8") (class "Default")
      (node (ref "IC3") (pin "98") (pinfunction "PE1_98") (pintype "bidirectional"))
      (node (ref "J13") (pin "9") (pinfunction "9_9") (pintype "passive"))
    )
    (net (code "26") (name "/DIGITAL9") (class "Default")
      (node (ref "IC3") (pin "97") (pinfunction "PE0_97") (pintype "bidirectional"))
      (node (ref "J13") (pin "10") (pinfunction "10_10") (pintype "passive"))
    )
    (net (code "27") (name "/DIGITAL10") (class "Default")
      (node (ref "IC3") (pin "91") (pinfunction "PB5_91") (pintype "bidirectional"))
      (node (ref "J13") (pin "11") (pinfunction "11_11") (pintype "passive"))
    )
    (net (code "28") (name "/DIGITAL11") (class "Default")
      (node (ref "IC3") (pin "90") (pinfunction "PB4_90") (pintype "bidirectional"))
      (node (ref "J13") (pin "12") (pinfunction "12_12") (pintype "passive"))
    )
    (net (code "29") (name "/DIGITAL12") (class "Default")
      (node (ref "IC3") (pin "88") (pinfunction "PD7_88") (pintype "bidirectional"))
      (node (ref "J13") (pin "13") (pinfunction "13_13") (pintype "passive"))
    )
    (net (code "30") (name "/DIGITAL13") (class "Default")
      (node (ref "IC3") (pin "85") (pinfunction "PD4_85") (pintype "bidirectional"))
      (node (ref "J13") (pin "14") (pinfunction "14_14") (pintype "passive"))
    )
    (net (code "31") (name "/DIGITAL14") (class "Default")
      (node (ref "IC3") (pin "84") (pinfunction "PD3_84") (pintype "bidirectional"))
      (node (ref "J13") (pin "15") (pinfunction "15_15") (pintype "passive"))
    )
    (net (code "32") (name "/I2C1_SCL") (class "Default")
      (node (ref "IC3") (pin "95") (pinfunction "PB8_95") (pintype "bidirectional"))
      (node (ref "J4") (pin "1") (pinfunction "1_1") (pintype "passive"))
      (node (ref "R23") (pin "1") (pinfunction "1_1") (pintype "passive"))
      (node (ref "U4") (pin "23") (pinfunction "SCL_23") (pintype "bidirectional"))
      (node (ref "U9") (pin "P$4") (pinfunction "SCL_P$4") (pintype "bidirectional"))
    )
    (net (code "33") (name "/I2C1_SDA") (class "Default")
      (node (ref "IC3") (pin "96") (pinfunction "PB9_96") (pintype "bidirectional"))
      (node (ref "J4") (pin "2") (pinfunction "2_2") (pintype "passive"))
      (node (ref "R22") (pin "1") (pinfunction "1_1") (pintype "passive"))
      (node (ref "U4") (pin "24") (pinfunction "SDA_24") (pintype "bidirectional"))
      (node (ref "U9") (pin "P$2") (pinfunction "SDA_P$2") (pintype "bidirectional"))
    )
    (net (code "34") (name "/I2C2_SCL{slash}USART3_TX") (class "Default")
      (node (ref "IC3") (pin "47") (pinfunction "PB10_47") (pintype "bidirectional"))
      (node (ref "J1") (pin "1") (pinfunction "1_1") (pintype "passive"))
      (node (ref "J2") (pin "1") (pinfunction "1_1") (pintype "passive"))
      (node (ref "R25") (pin "1") (pinfunction "1_1") (pintype "passive"))
      (node (ref "XB1") (pin "3") (pinfunction "DIN/~{CONFIG}_3") (pintype "input"))
    )
    (net (code "35") (name "/I2C2_SDA{slash}USART3_RX") (class "Default")
      (node (ref "IC3") (pin "48") (pinfunction "PB11_48") (pintype "bidirectional"))
      (node (ref "J1") (pin "2") (pinfunction "2_2") (pintype "passive"))
      (node (ref "J2") (pin "2") (pinfunction "2_2") (pintype "passive"))
      (node (ref "R24") (pin "1") (pinfunction "1_1") (pintype "passive"))
      (node (ref "XB1") (pin "2") (pinfunction "DOUT_2") (pintype "output"))
    )
    (net (code "36") (name "/LCD_E") (class "Default")
      (node (ref "IC3") (pin "81") (pinfunction "PD0_81") (pintype "bidirectional"))
      (node (ref "LCD") (pin "E") (pinfunction "E_E") (pintype "bidirectional"))
    )
    (net (code "37") (name "/LCD_RS") (class "Default")
      (node (ref "IC3") (pin "82") (pinfunction "PD1_82") (pintype "bidirectional"))
      (node (ref "LCD") (pin "RS") (pinfunction "RS_RS") (pintype "bidirectional"))
    )
    (net (code "38") (name "/LED0") (class "Default")
      (node (ref "IC3") (pin "46") (pinfunction "PE15_46") (pintype "bidirectional"))
      (node (ref "R20") (pin "2") (pinfunction "2_2") (pintype "passive"))
    )
    (net (code "39") (name "/LED1") (class "Default")
      (node (ref "R21") (pin "2") (pinfunction "2_2") (pintype "passive"))
    )
    (net (code "40") (name "/LED2") (class "Default")
      (node (ref "IC3") (pin "77") (pinfunction "PA15_77") (pintype "bidirectional"))
    )
    (net (code "41") (name "/M1_A") (class "Default")
      (node (ref "IC3") (pin "38") (pinfunction "PE7_38") (pintype "bidirectional"))
      (node (ref "U1") (pin "P$43") (pinfunction "IN1_P$43") (pintype "bidirectional"))
    )
    (net (code "42") (name "/M1_B") (class "Default")
      (node (ref "IC3") (pin "39") (pinfunction "PE8_39") (pintype "bidirectional"))
      (node (ref "U1") (pin "P$42") (pinfunction "IN2_P$42") (pintype "bidirectional"))
    )
    (net (code "43") (name "/M1_EN") (class "Default")
      (node (ref "IC3") (pin "40") (pinfunction "PE9_40") (pintype "bidirectional"))
      (node (ref "U1") (pin "P$3") (pinfunction "EN_D2_P$3") (pintype "bidirectional"))
    )
    (net (code "44") (name "/M1_FAULT") (class "Default")
      (node (ref "IC3") (pin "55") (pinfunction "PD8_55") (pintype "bidirectional"))
      (node (ref "R5") (pin "1") (pinfunction "1_1") (pintype "passive"))
      (node (ref "U1") (pin "P$44") (pinfunction "SFA_P$44") (pintype "bidirectional"))
    )
    (net (code "45") (name "/M1_SENSE") (class "Default")
      (node (ref "C10") (pin "1") (pinfunction "1_1") (pintype "passive"))
      (node (ref "IC3") (pin "35") (pinfunction "PB0_35") (pintype "bidirectional"))
      (node (ref "R8") (pin "2") (pinfunction "2_2") (pintype "passive"))
      (node (ref "U1") (pin "P$2") (pinfunction "FBA_P$2") (pintype "bidirectional"))
    )
    (net (code "46") (name "/M2_A") (class "Default")
      (node (ref "IC3") (pin "41") (pinfunction "PE10_41") (pintype "bidirectional"))
      (node (ref "U1") (pin "P$20") (pinfunction "IN4_P$20") (pintype "bidirectional"))
    )
    (net (code "47") (name "/M2_B") (class "Default")
      (node (ref "IC3") (pin "43") (pinfunction "PE12_43") (pintype "bidirectional"))
      (node (ref "U1") (pin "P$21") (pinfunction "IN3_P$21") (pintype "bidirectional"))
    )
    (net (code "48") (name "/M2_EN") (class "Default")
      (node (ref "IC3") (pin "42") (pinfunction "PE11_42") (pintype "bidirectional"))
      (node (ref "U1") (pin "P$25") (pinfunction "EN_D4_P$25") (pintype "bidirectional"))
    )
    (net (code "49") (name "/M2_FAULT") (class "Default")
      (node (ref "IC3") (pin "56") (pinfunction "PD9_56") (pintype "bidirectional"))
      (node (ref "R6") (pin "2") (pinfunction "2_2") (pintype "passive"))
      (node (ref "U1") (pin "P$22") (pinfunction "SFB_P$22") (pintype "bidirectional"))
    )
    (net (code "50") (name "/M2_SENSE") (class "Default")
      (node (ref "C11") (pin "1") (pinfunction "1_1") (pintype "passive"))
      (node (ref "IC3") (pin "36") (pinfunction "PB1_36") (pintype "bidirectional"))
      (node (ref "R9") (pin "2") (pinfunction "2_2") (pintype "passive"))
      (node (ref "U1") (pin "P$24") (pinfunction "FBB_P$24") (pintype "bidirectional"))
    )
    (net (code "51") (name "/MPOWER") (class "Default")
      (node (ref "C26") (pin "1") (pinfunction "1_1") (pintype "passive"))
      (node (ref "C28") (pin "1") (pinfunction "1_1") (pintype "passive"))
      (node (ref "C31") (pin "1") (pinfunction "1_1") (pintype "passive"))
      (node (ref "C8") (pin "1") (pinfunction "1_1") (pintype "passive"))
      (node (ref "C9") (pin "2") (pinfunction "2_2") (pintype "passive"))
      (node (ref "LED1") (pin "A") (pinfunction "A_A") (pintype "passive"))
      (node (ref "Q5") (pin "10") (pinfunction "D2_10") (pintype "bidirectional"))
      (node (ref "Q5") (pin "5") (pinfunction "D2_5") (pintype "bidirectional"))
      (node (ref "Q5") (pin "6") (pinfunction "D2_6") (pintype "bidirectional"))
      (node (ref "R10") (pin "2") (pinfunction "2_2") (pintype "passive"))
      (node (ref "R18") (pin "1") (pinfunction "1_1") (pintype "passive"))
      (node (ref "R34") (pin "2") (pinfunction "2_2") (pintype "passive"))
      (node (ref "U1") (pin "P$17") (pinfunction "VPWRB_1_P$17") (pintype "bidirectional"))
      (node (ref "U1") (pin "P$18") (pinfunction "VPWRB_2_P$18") (pintype "bidirectional"))
      (node (ref "U1") (pin "P$26") (pinfunction "VPWRB_3_P$26") (pintype "bidirectional"))
      (node (ref "U1") (pin "P$27") (pinfunction "VPWRB_4_P$27") (pintype "bidirectional"))
      (node (ref "U1") (pin "P$28") (pinfunction "VPWRB_5_P$28") (pintype "bidirectional"))
      (node (ref "U1") (pin "P$39") (pinfunction "VPWRA_4_P$39") (pintype "bidirectional"))
      (node (ref "U1") (pin "P$4") (pinfunction "VPWRA_1_P$4") (pintype "bidirectional"))
      (node (ref "U1") (pin "P$40") (pinfunction "VPWRA_5_P$40") (pintype "bidirectional"))
      (node (ref "U1") (pin "P$5") (pinfunction "VPWRA_2_P$5") (pintype "bidirectional"))
      (node (ref "U1") (pin "P$6") (pinfunction "VPWRA_3_P$6") (pintype "bidirectional"))
      (node (ref "U2") (pin "4") (pinfunction "VIN_4") (pintype "bidirectional"))
      (node (ref "U2") (pin "5") (pinfunction "VIN_5") (pintype "bidirectional"))
      (node (ref "U2") (pin "6") (pinfunction "VIN_6") (pintype "bidirectional"))
    )
    (net (code "52") (name "/OTG_FS_DM") (class "Default")
      (node (ref "C14") (pin "1") (pinfunction "1_1") (pintype "passive"))
      (node (ref "IC3") (pin "70") (pinfunction "PA11_70") (pintype "bidirectional"))
      (node (ref "U8") (pin "P$6") (pinfunction "IO1_2_P$6") (pintype "bidirectional"))
    )
    (net (code "53") (name "/OTG_FS_DP") (class "Default")
      (node (ref "C13") (pin "1") (pinfunction "1_1") (pintype "passive"))
      (node (ref "IC3") (pin "71") (pinfunction "PA12_71") (pintype "bidirectional"))
      (node (ref "U8") (pin "P$4") (pinfunction "IO2_2_P$4") (pintype "bidirectional"))
    )
    (net (code "54") (name "/OTG_FS_FAULT") (class "Default")
      (node (ref "IC3") (pin "69") (pinfunction "PA10_69") (pintype "bidirectional"))
      (node (ref "U7") (pin "3") (pinfunction "FLAGB_3") (pintype "bidirectional"))
    )
    (net (code "55") (name "/OTG_FS_ID") (class "Default")
      (node (ref "IC3") (pin "67") (pinfunction "PA8_67") (pintype "bidirectional"))
      (node (ref "USB2") (pin "ID") (pinfunction "ID_ID") (pintype "bidirectional"))
    )
    (net (code "56") (name "/OTG_FS_VBUS") (class "Default")
      (node (ref "IC3") (pin "68") (pinfunction "PA9_68") (pintype "bidirectional"))
      (node (ref "U7") (pin "4") (pinfunction "ENB_4") (pintype "bidirectional"))
    )
    (net (code "57") (name "/OTG_HS_DM") (class "Default")
      (node (ref "C18") (pin "1") (pinfunction "1_1") (pintype "passive"))
      (node (ref "IC3") (pin "53") (pinfunction "PB14_53") (pintype "bidirectional"))
      (node (ref "U6") (pin "P$6") (pinfunction "IO1_2_P$6") (pintype "bidirectional"))
    )
    (net (code "58") (name "/OTG_HS_DP") (class "Default")
      (node (ref "C17") (pin "1") (pinfunction "1_1") (pintype "passive"))
      (node (ref "IC3") (pin "54") (pinfunction "PB15_54") (pintype "bidirectional"))
      (node (ref "U6") (pin "P$4") (pinfunction "IO2_2_P$4") (pintype "bidirectional"))
    )
    (net (code "59") (name "/OTG_HS_FAULT") (class "Default")
      (node (ref "IC3") (pin "51") (pinfunction "PB12_51") (pintype "bidirectional"))
      (node (ref "U7") (pin "2") (pinfunction "FLAGA_2") (pintype "bidirectional"))
    )
    (net (code "60") (name "/OTG_HS_VBUS") (class "Default")
      (node (ref "IC3") (pin "52") (pinfunction "PB13_52") (pintype "bidirectional"))
      (node (ref "U7") (pin "1") (pinfunction "ENA_1") (pintype "bidirectional"))
    )
    (net (code "61") (name "/OUT1") (class "Default")
      (node (ref "LED6") (pin "2") (pinfunction "2_2") (pintype "passive"))
      (node (ref "LED6") (pin "3") (pinfunction "3_3") (pintype "passive"))
      (node (ref "MOTOR1") (pin "L") (pinfunction "L_L") (pintype "bidirectional"))
      (node (ref "U1") (pin "P$7") (pinfunction "OUT1_1_P$7") (pintype "bidirectional"))
      (node (ref "U1") (pin "P$8") (pinfunction "OUT1_2_P$8") (pintype "bidirectional"))
      (node (ref "U1") (pin "P$9") (pinfunction "OUT1_3_P$9") (pintype "bidirectional"))
    )
    (net (code "62") (name "/OUT2") (class "Default")
      (node (ref "MOTOR1") (pin "R") (pinfunction "R_R") (pintype "bidirectional"))
      (node (ref "R37") (pin "1") (pinfunction "1_1") (pintype "passive"))
      (node (ref "U1") (pin "P$36") (pinfunction "OUT2_1_P$36") (pintype "bidirectional"))
      (node (ref "U1") (pin "P$37") (pinfunction "OUT2_2_P$37") (pintype "bidirectional"))
      (node (ref "U1") (pin "P$38") (pinfunction "OUT2_3_P$38") (pintype "bidirectional"))
    )
    (net (code "63") (name "/OUT3") (class "Default")
      (node (ref "LED7") (pin "2") (pinfunction "2_2") (pintype "passive"))
      (node (ref "LED7") (pin "3") (pinfunction "3_3") (pintype "passive"))
      (node (ref "MOTOR2") (pin "L") (pinfunction "L_L") (pintype "bidirectional"))
      (node (ref "U1") (pin "P$29") (pinfunction "OUT3_1_P$29") (pintype "bidirectional"))
      (node (ref "U1") (pin "P$30") (pinfunction "OUT3_2_P$30") (pintype "bidirectional"))
      (node (ref "U1") (pin "P$31") (pinfunction "OUT3_3_P$31") (pintype "bidirectional"))
    )
    (net (code "64") (name "/OUT4") (class "Default")
      (node (ref "MOTOR2") (pin "R") (pinfunction "R_R") (pintype "bidirectional"))
      (node (ref "R38") (pin "1") (pinfunction "1_1") (pintype "passive"))
      (node (ref "U1") (pin "P$14") (pinfunction "OUT4_1_P$14") (pintype "bidirectional"))
      (node (ref "U1") (pin "P$15") (pinfunction "OUT4_2_P$15") (pintype "bidirectional"))
      (node (ref "U1") (pin "P$16") (pinfunction "OUT4_3_P$16") (pintype "bidirectional"))
    )
    (net (code "65") (name "/RAW_SPWR") (class "Default")
      (node (ref "C27") (pin "1") (pinfunction "1_1") (pintype "passive"))
      (node (ref "Q4") (pin "10") (pinfunction "D2_10") (pintype "bidirectional"))
      (node (ref "Q4") (pin "2") (pinfunction "G1_2") (pintype "bidirectional"))
      (node (ref "Q4") (pin "5") (pinfunction "D2_5") (pintype "bidirectional"))
      (node (ref "Q4") (pin "6") (pinfunction "D2_6") (pintype "bidirectional"))
      (node (ref "R29") (pin "1") (pinfunction "1_1") (pintype "passive"))
      (node (ref "R36") (pin "2") (pinfunction "2_2") (pintype "passive"))
      (node (ref "SERVO_PWR") (pin "L") (pinfunction "L_L") (pintype "bidirectional"))
    )
    (net (code "66") (name "/RESET") (class "Default")
      (node (ref "C30") (pin "2") (pinfunction "2_2") (pintype "passive"))
      (node (ref "IC3") (pin "14") (pinfunction "NRST_14") (pintype "input"))
      (node (ref "R7") (pin "1") (pinfunction "1_1") (pintype "passive"))
      (node (ref "RESET") (pin "1") (pinfunction "S_1") (pintype "passive"))
      (node (ref "RESET") (pin "2") (pinfunction "S1_2") (pintype "passive"))
    )
    (net (code "67") (name "/SDIO_CK") (class "Default")
      (node (ref "IC3") (pin "80") (pinfunction "PC12_80") (pintype "bidirectional"))
      (node (ref "SD") (pin "5") (pinfunction "SCK_5") (pintype "bidirectional"))
    )
    (net (code "68") (name "/SDIO_CMD") (class "Default")
      (node (ref "IC3") (pin "83") (pinfunction "PD2_83") (pintype "bidirectional"))
      (node (ref "SD") (pin "3") (pinfunction "DI_3") (pintype "bidirectional"))
    )
    (net (code "69") (name "/SDIO_D0") (class "Default")
      (node (ref "IC3") (pin "65") (pinfunction "PC8_65") (pintype "bidirectional"))
      (node (ref "R13") (pin "2") (pinfunction "2_2") (pintype "passive"))
      (node (ref "SD") (pin "7") (pinfunction "DO_7") (pintype "bidirectional"))
    )
    (net (code "70") (name "/SDIO_D1") (class "Default")
      (node (ref "IC3") (pin "66") (pinfunction "PC9_66") (pintype "bidirectional"))
      (node (ref "R14") (pin "2") (pinfunction "2_2") (pintype "passive"))
      (node (ref "SD") (pin "8") (pinfunction "RSV_8") (pintype "bidirectional"))
    )
    (net (code "71") (name "/SDIO_D2") (class "Default")
      (node (ref "IC3") (pin "78") (pinfunction "PC10_78") (pintype "bidirectional"))
      (node (ref "R15") (pin "1") (pinfunction "1_1") (pintype "passive"))
      (node (ref "SD") (pin "1") (pinfunction "NC_1") (pintype "bidirectional"))
    )
    (net (code "72") (name "/SDIO_D3") (class "Default")
      (node (ref "IC3") (pin "79") (pinfunction "PC11_79") (pintype "bidirectional"))
      (node (ref "R12") (pin "2") (pinfunction "2_2") (pintype "passive"))
      (node (ref "SD") (pin "2") (pinfunction "CS_2") (pintype "bidirectional"))
    )
    (net (code "73") (name "/SERVO0") (class "Default")
      (node (ref "IC3") (pin "64") (pinfunction "PC7_64") (pintype "bidirectional"))
      (node (ref "J16") (pin "1") (pinfunction "1_1") (pintype "passive"))
    )
    (net (code "74") (name "/SERVO1") (class "Default")
      (node (ref "IC3") (pin "63") (pinfunction "PC6_63") (pintype "bidirectional"))
      (node (ref "J16") (pin "2") (pinfunction "2_2") (pintype "passive"))
    )
    (net (code "75") (name "/SERVO2") (class "Default")
      (node (ref "IC3") (pin "62") (pinfunction "PD15_62") (pintype "bidirectional"))
      (node (ref "J16") (pin "3") (pinfunction "3_3") (pintype "passive"))
    )
    (net (code "76") (name "/SERVO3") (class "Default")
      (node (ref "IC3") (pin "61") (pinfunction "PD14_61") (pintype "bidirectional"))
      (node (ref "J16") (pin "4") (pinfunction "4_4") (pintype "passive"))
    )
    (net (code "77") (name "/SERVO4") (class "Default")
      (node (ref "IC3") (pin "60") (pinfunction "PD13_60") (pintype "bidirectional"))
      (node (ref "J16") (pin "5") (pinfunction "5_5") (pintype "passive"))
    )
    (net (code "78") (name "/SERVO5") (class "Default")
      (node (ref "IC3") (pin "59") (pinfunction "PD12_59") (pintype "bidirectional"))
      (node (ref "J16") (pin "6") (pinfunction "6_6") (pintype "passive"))
    )
    (net (code "79") (name "/SERVO6") (class "Default")
      (node (ref "IC3") (pin "45") (pinfunction "PE14_45") (pintype "bidirectional"))
      (node (ref "J16") (pin "7") (pinfunction "7_7") (pintype "passive"))
    )
    (net (code "80") (name "/SERVO7") (class "Default")
      (node (ref "IC3") (pin "44") (pinfunction "PE13_44") (pintype "bidirectional"))
      (node (ref "J16") (pin "8") (pinfunction "8_8") (pintype "passive"))
    )
    (net (code "81") (name "/SERVO_SENSE") (class "Default")
      (node (ref "IC3") (pin "34") (pinfunction "PC5_34") (pintype "bidirectional"))
      (node (ref "R40") (pin "2") (pinfunction "2_2") (pintype "passive"))
      (node (ref "R41") (pin "1") (pinfunction "1_1") (pintype "passive"))
    )
    (net (code "82") (name "/SPI1_MISO") (class "Default")
      (node (ref "IC3") (pin "31") (pinfunction "PA6_31") (pintype "bidirectional"))
      (node (ref "J5") (pin "4") (pinfunction "4_4") (pintype "passive"))
    )
    (net (code "83") (name "/SPI1_MOSI") (class "Default")
      (node (ref "IC3") (pin "32") (pinfunction "PA7_32") (pintype "bidirectional"))
      (node (ref "J5") (pin "3") (pinfunction "3_3") (pintype "passive"))
    )
    (net (code "84") (name "/SPI1_NSS") (class "Default")
      (node (ref "IC3") (pin "29") (pinfunction "PA4_29") (pintype "bidirectional"))
      (node (ref "J5") (pin "2") (pinfunction "2_2") (pintype "passive"))
    )
    (net (code "85") (name "/SPI1_SCK") (class "Default")
      (node (ref "IC3") (pin "30") (pinfunction "PA5_30") (pintype "bidirectional"))
      (node (ref "J5") (pin "5") (pinfunction "5_5") (pintype "passive"))
    )
    (net (code "86") (name "/SPWR") (class "Default")
      (node (ref "J15") (pin "1") (pinfunction "1_1") (pintype "passive"))
      (node (ref "J15") (pin "2") (pinfunction "2_2") (pintype "passive"))
      (node (ref "J15") (pin "3") (pinfunction "3_3") (pintype "passive"))
      (node (ref "J15") (pin "4") (pinfunction "4_4") (pintype "passive"))
      (node (ref "J15") (pin "5") (pinfunction "5_5") (pintype "passive"))
      (node (ref "J15") (pin "6") (pinfunction "6_6") (pintype "passive"))
      (node (ref "J15") (pin "7") (pinfunction "7_7") (pintype "passive"))
      (node (ref "J15") (pin "8") (pinfunction "8_8") (pintype "passive"))
      (node (ref "Q4") (pin "1") (pinfunction "S1_1") (pintype "bidirectional"))
      (node (ref "Q4") (pin "3") (pinfunction "S2_3") (pintype "bidirectional"))
      (node (ref "R40") (pin "1") (pinfunction "1_1") (pintype "passive"))
    )
    (net (code "87") (name "/SWDCLK") (class "Default")
      (node (ref "IC3") (pin "76") (pinfunction "PA14_76") (pintype "bidirectional"))
      (node (ref "J7") (pin "3") (pinfunction "3_3") (pintype "passive"))
    )
    (net (code "88") (name "/SWDIO") (class "Default")
      (node (ref "IC3") (pin "72") (pinfunction "PA13_72") (pintype "bidirectional"))
      (node (ref "J7") (pin "1") (pinfunction "1_1") (pintype "passive"))
    )
    (net (code "89") (name "/USART1_RX") (class "Default")
      (node (ref "IC3") (pin "93") (pinfunction "PB7_93") (pintype "bidirectional"))
      (node (ref "J6") (pin "3") (pinfunction "3_3") (pintype "passive"))
    )
    (net (code "90") (name "/USART1_TX") (class "Default")
      (node (ref "IC3") (pin "92") (pinfunction "PB6_92") (pintype "bidirectional"))
      (node (ref "J6") (pin "2") (pinfunction "2_2") (pintype "passive"))
    )
    (net (code "91") (name "/USART2_RX") (class "Default")
      (node (ref "IC3") (pin "87") (pinfunction "PD6_87") (pintype "bidirectional"))
      (node (ref "J3") (pin "2") (pinfunction "2_2") (pintype "passive"))
    )
    (net (code "92") (name "/USART2_TX") (class "Default")
      (node (ref "IC3") (pin "86") (pinfunction "PD5_86") (pintype "bidirectional"))
      (node (ref "J3") (pin "1") (pinfunction "1_1") (pintype "passive"))
    )
    (net (code "93") (name "/USB_5V") (class "Default")
      (node (ref "C22") (pin "2") (pinfunction "2_2") (pintype "passive"))
      (node (ref "C24") (pin "2") (pinfunction "2_2") (pintype "passive"))
      (node (ref "Q1") (pin "3") (pinfunction "D_3") (pintype "passive"))
      (node (ref "U7") (pin "5") (pinfunction "OUTB_5") (pintype "bidirectional"))
      (node (ref "USB2") (pin "VBUS") (pinfunction "VBUS_VBUS") (pintype "bidirectional"))
    )
    (net (code "94") (name "GND") (class "Default")
      (node (ref "BTN1") (pin "3") (pinfunction "P_3") (pintype "passive"))
      (node (ref "BTN1") (pin "4") (pinfunction "P1_4") (pintype "passive"))
      (node (ref "BTN2") (pin "3") (pinfunction "P_3") (pintype "passive"))
      (node (ref "BTN2") (pin "4") (pinfunction "P1_4") (pintype "passive"))
      (node (ref "C1") (pin "2") (pinfunction "2_2") (pintype "passive"))
      (node (ref "C10") (pin "2") (pinfunction "2_2") (pintype "passive"))
      (node (ref "C11") (pin "2") (pinfunction "2_2") (pintype "passive"))
      (node (ref "C12") (pin "2") (pinfunction "2_2") (pintype "passive"))
      (node (ref "C13") (pin "2") (pinfunction "2_2") (pintype "passive"))
      (node (ref "C14") (pin "2") (pinfunction "2_2") (pintype "passive"))
      (node (ref "C15") (pin "2") (pinfunction "2_2") (pintype "passive"))
      (node (ref "C16") (pin "2") (pinfunction "2_2") (pintype "passive"))
      (node (ref "C17") (pin "2") (pinfunction "2_2") (pintype "passive"))
      (node (ref "C18") (pin "2") (pinfunction "2_2") (pintype "passive"))
      (node (ref "C19") (pin "2") (pinfunction "2_2") (pintype "passive"))
      (node (ref "C2") (pin "2") (pinfunction "2_2") (pintype "passive"))
      (node (ref "C20") (pin "1") (pinfunction "1_1") (pintype "passive"))
      (node (ref "C21") (pin "2") (pinfunction "2_2") (pintype "passive"))
      (node (ref "C22") (pin "1") (pinfunction "1_1") (pintype "passive"))
      (node (ref "C23") (pin "2") (pinfunction "2_2") (pintype "passive"))
      (node (ref "C24") (pin "1") (pinfunction "1_1") (pintype "passive"))
      (node (ref "C25") (pin "2") (pinfunction "2_2") (pintype "passive"))
      (node (ref "C26") (pin "2") (pinfunction "2_2") (pintype "passive"))
      (node (ref "C27") (pin "2") (pinfunction "2_2") (pintype "passive"))
      (node (ref "C28") (pin "2") (pinfunction "2_2") (pintype "passive"))
      (node (ref "C3") (pin "2") (pinfunction "2_2") (pintype "passive"))
      (node (ref "C31") (pin "2") (pinfunction "2_2") (pintype "passive"))
      (node (ref "C33") (pin "1") (pinfunction "1_1") (pintype "passive"))
      (node (ref "C34") (pin "2") (pinfunction "2_2") (pintype "passive"))
      (node (ref "C35") (pin "2") (pinfunction "2_2") (pintype "passive"))
      (node (ref "C36") (pin "2") (pinfunction "2_2") (pintype "passive"))
      (node (ref "C37") (pin "2") (pinfunction "2_2") (pintype "passive"))
      (node (ref "C4") (pin "2") (pinfunction "2_2") (pintype "passive"))
      (node (ref "C5") (pin "2") (pinfunction "2_2") (pintype "passive"))
      (node (ref "C6") (pin "2") (pinfunction "2_2") (pintype "passive"))
      (node (ref "C7") (pin "1") (pinfunction "1_1") (pintype "passive"))
      (node (ref "IC3") (pin "10") (pinfunction "VSS_5_10") (pintype "power_in"))
      (node (ref "IC3") (pin "20") (pinfunction "VSSA_20") (pintype "power_in"))
      (node (ref "IC3") (pin "27") (pinfunction "VSS_4_27") (pintype "power_in"))
      (node (ref "IC3") (pin "6") (pinfunction "VBAT_6") (pintype "power_in"))
      (node (ref "IC3") (pin "74") (pinfunction "VSS_2_74") (pintype "power_in"))
      (node (ref "IC3") (pin "99") (pinfunction "VSS_6_99") (pintype "power_in"))
      (node (ref "IC4") (pin "4") (pinfunction "V-_4") (pintype "power_in"))
      (node (ref "J1") (pin "3") (pinfunction "3_3") (pintype "passive"))
      (node (ref "J11") (pin "1") (pinfunction "1_1") (pintype "passive"))
      (node (ref "J11") (pin "10") (pinfunction "10_10") (pintype "passive"))
      (node (ref "J11") (pin "11") (pinfunction "11_11") (pintype "passive"))
      (node (ref "J11") (pin "12") (pinfunction "12_12") (pintype "passive"))
      (node (ref "J11") (pin "13") (pinfunction "13_13") (pintype "passive"))
      (node (ref "J11") (pin "14") (pinfunction "14_14") (pintype "passive"))
      (node (ref "J11") (pin "15") (pinfunction "15_15") (pintype "passive"))
      (node (ref "J11") (pin "2") (pinfunction "2_2") (pintype "passive"))
      (node (ref "J11") (pin "3") (pinfunction "3_3") (pintype "passive"))
      (node (ref "J11") (pin "4") (pinfunction "4_4") (pintype "passive"))
      (node (ref "J11") (pin "5") (pinfunction "5_5") (pintype "passive"))
      (node (ref "J11") (pin "6") (pinfunction "6_6") (pintype "passive"))
      (node (ref "J11") (pin "7") (pinfunction "7_7") (pintype "passive"))
      (node (ref "J11") (pin "8") (pinfunction "8_8") (pintype "passive"))
      (node (ref "J11") (pin "9") (pinfunction "9_9") (pintype "passive"))
      (node (ref "J14") (pin "1") (pinfunction "1_1") (pintype "passive"))
      (node (ref "J14") (pin "2") (pinfunction "2_2") (pintype "passive"))
      (node (ref "J14") (pin "3") (pinfunction "3_3") (pintype "passive"))
      (node (ref "J14") (pin "4") (pinfunction "4_4") (pintype "passive"))
      (node (ref "J14") (pin "5") (pinfunction "5_5") (pintype "passive"))
      (node (ref "J14") (pin "6") (pinfunction "6_6") (pintype "passive"))
      (node (ref "J14") (pin "7") (pinfunction "7_7") (pintype "passive"))
      (node (ref "J14") (pin "8") (pinfunction "8_8") (pintype "passive"))
      (node (ref "J2") (pin "3") (pinfunction "3_3") (pintype "passive"))
      (node (ref "J3") (pin "3") (pinfunction "3_3") (pintype "passive"))
      (node (ref "J4") (pin "3") (pinfunction "3_3") (pintype "passive"))
      (node (ref "J5") (pin "1") (pinfunction "1_1") (pintype "passive"))
      (node (ref "J6") (pin "4") (pinfunction "4_4") (pintype "passive"))
      (node (ref "J7") (pin "2") (pinfunction "2_2") (pintype "passive"))
      (node (ref "J8") (pin "1") (pinfunction "1_1") (pintype "passive"))
      (node (ref "J8") (pin "2") (pinfunction "2_2") (pintype "passive"))
      (node (ref "J8") (pin "3") (pinfunction "3_3") (pintype "passive"))
      (node (ref "J8") (pin "4") (pinfunction "4_4") (pintype "passive"))
      (node (ref "J8") (pin "5") (pinfunction "5_5") (pintype "passive"))
      (node (ref "J8") (pin "6") (pinfunction "6_6") (pintype "passive"))
      (node (ref "J8") (pin "7") (pinfunction "7_7") (pintype "passive"))
      (node (ref "J8") (pin "8") (pinfunction "8_8") (pintype "passive"))
      (node (ref "LCD") (pin "K") (pinfunction "K_K") (pintype "bidirectional"))
      (node (ref "LCD") (pin "R/W") (pinfunction "R/W_R/W") (pintype "bidirectional"))
      (node (ref "LCD") (pin "VSS") (pinfunction "VSS_VSS") (pintype "bidirectional"))
      (node (ref "LED2") (pin "C") (pinfunction "C_C") (pintype "passive"))
      (node (ref "LED3") (pin "C") (pinfunction "C_C") (pintype "passive"))
      (node (ref "LED4") (pin "C") (pinfunction "C_C") (pintype "passive"))
      (node (ref "POT") (pin "3") (pinfunction "E_3") (pintype "passive"))
      (node (ref "POWER") (pin "R") (pinfunction "R_R") (pintype "bidirectional"))
      (node (ref "Q2") (pin "2") (pinfunction "E_2") (pintype "passive"))
      (node (ref "Q3") (pin "1") (pinfunction "S_1") (pintype "bidirectional"))
      (node (ref "Q3") (pin "2") (pinfunction "S_2") (pintype "bidirectional"))
      (node (ref "Q3") (pin "3") (pinfunction "S_3") (pintype "bidirectional"))
      (node (ref "R11") (pin "1") (pinfunction "1_1") (pintype "passive"))
      (node (ref "R19") (pin "2") (pinfunction "2_2") (pintype "passive"))
      (node (ref "R2") (pin "2") (pinfunction "2_2") (pintype "passive"))
      (node (ref "R26") (pin "1") (pinfunction "1_1") (pintype "passive"))
      (node (ref "R28") (pin "2") (pinfunction "2_2") (pintype "passive"))
      (node (ref "R30") (pin "1") (pinfunction "1_1") (pintype "passive"))
      (node (ref "R33") (pin "1") (pinfunction "1_1") (pintype "passive"))
      (node (ref "R35") (pin "1") (pinfunction "1_1") (pintype "passive"))
      (node (ref "R41") (pin "2") (pinfunction "2_2") (pintype "passive"))
      (node (ref "R42") (pin "1") (pinfunction "1_1") (pintype "passive"))
      (node (ref "R43") (pin "1") (pinfunction "1_1") (pintype "passive"))
      (node (ref "R8") (pin "1") (pinfunction "1_1") (pintype "passive"))
      (node (ref "R9") (pin "1") (pinfunction "1_1") (pintype "passive"))
      (node (ref "RESET") (pin "3") (pinfunction "P_3") (pintype "passive"))
      (node (ref "RESET") (pin "4") (pinfunction "P1_4") (pintype "passive"))
      (node (ref "SD") (pin "6") (pinfunction "GND_6") (pintype "bidirectional"))
      (node (ref "SD") (pin "GND1") (pinfunction "SHIELD_GND1") (pintype "bidirectional"))
      (node (ref "SD") (pin "GND3") (pinfunction "SHIELD_GND3") (pintype "bidirectional"))
      (node (ref "SERVO_PWR") (pin "R") (pinfunction "R_R") (pintype "bidirectional"))
      (node (ref "SW1") (pin "P$2") (pinfunction "P$2_P$2") (pintype "bidirectional"))
      (node (ref "U1") (pin "P$1") (pinfunction "D1_P$1") (pintype "bidirectional"))
      (node (ref "U1") (pin "P$10") (pinfunction "PGNDA_1_P$10") (pintype "bidirectional"))
      (node (ref "U1") (pin "P$11") (pinfunction "PGNDA_2_P$11") (pintype "bidirectional"))
      (node (ref "U1") (pin "P$12") (pinfunction "PGNDB_1_P$12") (pintype "bidirectional"))
      (node (ref "U1") (pin "P$13") (pinfunction "PGNDB_2_P$13") (pintype "bidirectional"))
      (node (ref "U1") (pin "P$23") (pinfunction "D3_P$23") (pintype "bidirectional"))
      (node (ref "U1") (pin "P$32") (pinfunction "PGNDB_3_P$32") (pintype "bidirectional"))
      (node (ref "U1") (pin "P$33") (pinfunction "PGNDB_4_P$33") (pintype "bidirectional"))
      (node (ref "U1") (pin "P$34") (pinfunction "PGNDA_3_P$34") (pintype "bidirectional"))
      (node (ref "U1") (pin "P$35") (pinfunction "PGNDA_4_P$35") (pintype "bidirectional"))
      (node (ref "U1") (pin "P$45") (pinfunction "GND_P$45") (pintype "bidirectional"))
      (node (ref "U1") (pin "P$46") (pinfunction "GND_P$46") (pintype "bidirectional"))
      (node (ref "U1") (pin "P$47") (pinfunction "GND_P$47") (pintype "bidirectional"))
      (node (ref "U2") (pin "14") (pinfunction "GND_14") (pintype "bidirectional"))
      (node (ref "U2") (pin "P$1") (pinfunction "GND_P$1") (pintype "bidirectional"))
      (node (ref "U3") (pin "3") (pinfunction "GND_3") (pintype "bidirectional"))
      (node (ref "U4") (pin "1") (pinfunction "CLKIN_1") (pintype "bidirectional"))
      (node (ref "U4") (pin "11") (pinfunction "FSYNC_11") (pintype "bidirectional"))
      (node (ref "U4") (pin "18") (pinfunction "GND_18") (pintype "bidirectional"))
      (node (ref "U4") (pin "9") (pinfunction "AD0_9") (pintype "bidirectional"))
      (node (ref "U5") (pin "GND") (pinfunction "GND_GND") (pintype "bidirectional"))
      (node (ref "U6") (pin "P$2") (pinfunction "GND_P$2") (pintype "bidirectional"))
      (node (ref "U7") (pin "6") (pinfunction "GND_6") (pintype "bidirectional"))
      (node (ref "U8") (pin "P$2") (pinfunction "GND_P$2") (pintype "bidirectional"))
      (node (ref "U9") (pin "P$12") (pinfunction "ADDR_P$12") (pintype "bidirectional"))
      (node (ref "U9") (pin "P$18") (pinfunction "GND_P$18") (pintype "bidirectional"))
      (node (ref "U9") (pin "P$21") (pinfunction "GND_P$21") (pintype "bidirectional"))
      (node (ref "U9") (pin "P$8") (pinfunction "GND_P$8") (pintype "bidirectional"))
      (node (ref "USB1") (pin "GND") (pinfunction "GND_GND") (pintype "bidirectional"))
      (node (ref "USB1") (pin "GND@1") (pinfunction "GND_GND@1") (pintype "bidirectional"))
      (node (ref "USB1") (pin "GND@2") (pinfunction "GND_GND@2") (pintype "bidirectional"))
      (node (ref "USB2") (pin "GND") (pinfunction "GND_GND") (pintype "bidirectional"))
      (node (ref "USB2") (pin "MTN1") (pinfunction "MTN2_MTN1") (pintype "bidirectional"))
      (node (ref "USB2") (pin "MTN2") (pinfunction "MTN3_MTN2") (pintype "bidirectional"))
      (node (ref "USB2") (pin "MTN3") (pinfunction "MTN1_MTN3") (pintype "bidirectional"))
      (node (ref "USB2") (pin "MTN4") (pinfunction "MTN4_MTN4") (pintype "bidirectional"))
      (node (ref "XB1") (pin "10") (pinfunction "GND_10") (pintype "power_in"))
    )
    (net (code "95") (name "Net-(IC3A-VCAP_2)") (class "Default")
      (node (ref "C37") (pin "1") (pinfunction "1_1") (pintype "passive"))
      (node (ref "IC3") (pin "73") (pinfunction "VCAP_2_73") (pintype "power_in"))
    )
    (net (code "96") (name "Net-(IC3B-OSC_IN)") (class "Default")
      (node (ref "C19") (pin "1") (pinfunction "1_1") (pintype "passive"))
      (node (ref "IC3") (pin "12") (pinfunction "OSC_IN_12") (pintype "input"))
      (node (ref "Y1") (pin "2") (pinfunction "2_2") (pintype "passive"))
    )
    (net (code "97") (name "Net-(IC3B-OSC_OUT)") (class "Default")
      (node (ref "C20") (pin "2") (pinfunction "2_2") (pintype "passive"))
      (node (ref "IC3") (pin "13") (pinfunction "OSC_OUT_13") (pintype "output"))
      (node (ref "Y1") (pin "1") (pinfunction "1_1") (pintype "passive"))
    )
    (net (code "98") (name "Net-(IC3M-VCAP_1)") (class "Default")
      (node (ref "C7") (pin "2") (pinfunction "2_2") (pintype "passive"))
      (node (ref "IC3") (pin "49") (pinfunction "VCAP_1_49") (pintype "power_in"))
    )
    (net (code "99") (name "Net-(IC4A-+IN)") (class "Default")
      (node (ref "IC4") (pin "3") (pinfunction "+IN_3") (pintype "input"))
      (node (ref "R10") (pin "1") (pinfunction "1_1") (pintype "passive"))
      (node (ref "R11") (pin "2") (pinfunction "2_2") (pintype "passive"))
    )
    (net (code "100") (name "Net-(IC4A-OUT)") (class "Default")
      (node (ref "IC4") (pin "1") (pinfunction "OUT_1") (pintype "output"))
      (node (ref "Q1") (pin "1") (pinfunction "G_1") (pintype "passive"))
    )
    (net (code "101") (name "Net-(IC4B-+IN)") (class "Default")
      (node (ref "IC4") (pin "5") (pinfunction "+IN_5") (pintype "input"))
      (node (ref "R28") (pin "1") (pinfunction "1_1") (pintype "passive"))
      (node (ref "R29") (pin "2") (pinfunction "2_2") (pintype "passive"))
    )
    (net (code "102") (name "Net-(IC4B--IN)") (class "Default")
      (node (ref "IC4") (pin "6") (pinfunction "-IN_6") (pintype "input"))
      (node (ref "R26") (pin "2") (pinfunction "2_2") (pintype "passive"))
      (node (ref "R27") (pin "1") (pinfunction "1_1") (pintype "passive"))
    )
    (net (code "103") (name "Net-(IC4B-OUT)") (class "Default")
      (node (ref "IC4") (pin "7") (pinfunction "OUT_7") (pintype "output"))
      (node (ref "R36") (pin "1") (pinfunction "1_1") (pintype "passive"))
      (node (ref "U3") (pin "2") (pinfunction "A_2") (pintype "bidirectional"))
    )
    (net (code "104") (name "Net-(J12-Pad1)") (class "Default")
      (node (ref "J12") (pin "1") (pinfunction "1_1") (pintype "passive"))
      (node (ref "J12") (pin "10") (pinfunction "10_10") (pintype "passive"))
      (node (ref "J12") (pin "11") (pinfunction "11_11") (pintype "passive"))
      (node (ref "J12") (pin "12") (pinfunction "12_12") (pintype "passive"))
      (node (ref "J12") (pin "13") (pinfunction "13_13") (pintype "passive"))
      (node (ref "J12") (pin "14") (pinfunction "14_14") (pintype "passive"))
      (node (ref "J12") (pin "15") (pinfunction "15_15") (pintype "passive"))
      (node (ref "J12") (pin "2") (pinfunction "2_2") (pintype "passive"))
      (node (ref "J12") (pin "3") (pinfunction "3_3") (pintype "passive"))
      (node (ref "J12") (pin "4") (pinfunction "4_4") (pintype "passive"))
      (node (ref "J12") (pin "5") (pinfunction "5_5") (pintype "passive"))
      (node (ref "J12") (pin "6") (pinfunction "6_6") (pintype "passive"))
      (node (ref "J12") (pin "7") (pinfunction "7_7") (pintype "passive"))
      (node (ref "J12") (pin "8") (pinfunction "8_8") (pintype "passive"))
      (node (ref "J12") (pin "9") (pinfunction "9_9") (pintype "passive"))
      (node (ref "JP2") (pin "2") (pinfunction "2_2") (pintype "passive"))
    )
    (net (code "105") (name "Net-(L1-1)") (class "Default")
      (node (ref "C32") (pin "2") (pinfunction "2_2") (pintype "passive"))
      (node (ref "L1") (pin "P$1") (pinfunction "1_P$1") (pintype "passive"))
      (node (ref "Q3") (pin "5") (pinfunction "D_5") (pintype "bidirectional"))
      (node (ref "Q3") (pin "6") (pinfunction "D_6") (pintype "bidirectional"))
      (node (ref "Q3") (pin "7") (pinfunction "D_7") (pintype "bidirectional"))
      (node (ref "Q3") (pin "8") (pinfunction "D_8") (pintype "bidirectional"))
      (node (ref "U2") (pin "10") (pinfunction "SW_10") (pintype "bidirectional"))
      (node (ref "U2") (pin "8") (pinfunction "SW_8") (pintype "bidirectional"))
      (node (ref "U2") (pin "9") (pinfunction "SW_9") (pintype "bidirectional"))
    )
    (net (code "106") (name "Net-(LCD-PadA)") (class "Default")
      (node (ref "LCD") (pin "A") (pinfunction "A_A") (pintype "bidirectional"))
      (node (ref "R1") (pin "1") (pinfunction "1_1") (pintype "passive"))
    )
    (net (code "107") (name "Net-(LED1-PadC)") (class "Default")
      (node (ref "LED1") (pin "C") (pinfunction "C_C") (pintype "passive"))
      (node (ref "R30") (pin "2") (pinfunction "2_2") (pintype "passive"))
    )
    (net (code "108") (name "Net-(LED2-PadA)") (class "Default")
      (node (ref "LED2") (pin "A") (pinfunction "A_A") (pintype "passive"))
      (node (ref "R20") (pin "1") (pinfunction "1_1") (pintype "passive"))
    )
    (net (code "109") (name "Net-(LED3-PadA)") (class "Default")
      (node (ref "LED3") (pin "A") (pinfunction "A_A") (pintype "passive"))
      (node (ref "R21") (pin "1") (pinfunction "1_1") (pintype "passive"))
    )
    (net (code "110") (name "Net-(LED4-PadA)") (class "Default")
      (node (ref "LED4") (pin "A") (pinfunction "A_A") (pintype "passive"))
      (node (ref "R4") (pin "1") (pinfunction "1_1") (pintype "passive"))
    )
    (net (code "111") (name "Net-(LED5-PadC)") (class "Default")
      (node (ref "LED5") (pin "C") (pinfunction "C_C") (pintype "passive"))
      (node (ref "R35") (pin "2") (pinfunction "2_2") (pintype "passive"))
    )
    (net (code "112") (name "Net-(LED6-Pad1)") (class "Default")
      (node (ref "LED6") (pin "1") (pinfunction "1_1") (pintype "passive"))
      (node (ref "LED6") (pin "4") (pinfunction "4_4") (pintype "passive"))
      (node (ref "R37") (pin "2") (pinfunction "2_2") (pintype "passive"))
    )
    (net (code "113") (name "Net-(LED7-Pad1)") (class "Default")
      (node (ref "LED7") (pin "1") (pinfunction "1_1") (pintype "passive"))
      (node (ref "LED7") (pin "4") (pinfunction "4_4") (pintype "passive"))
      (node (ref "R38") (pin "2") (pinfunction "2_2") (pintype "passive"))
    )
    (net (code "114") (name "Net-(POT-S)") (class "Default")
      (node (ref "LCD") (pin "VO") (pinfunction "VO_VO") (pintype "bidirectional"))
      (node (ref "POT") (pin "2") (pinfunction "S_2") (pintype "passive"))
    )
    (net (code "115") (name "Net-(POWER-PadL)") (class "Default")
      (node (ref "POWER") (pin "L") (pinfunction "L_L") (pintype "bidirectional"))
      (node (ref "Q5") (pin "7") (pinfunction "D1_7") (pintype "bidirectional"))
      (node (ref "Q5") (pin "8") (pinfunction "D1_8") (pintype "bidirectional"))
      (node (ref "Q5") (pin "9") (pinfunction "D1_9") (pintype "bidirectional"))
    )
    (net (code "116") (name "Net-(Q1-S)") (class "Default")
      (node (ref "F1") (pin "1") (pinfunction "1_1") (pintype "bidirectional"))
      (node (ref "Q1") (pin "2") (pinfunction "S_2") (pintype "passive"))
    )
    (net (code "117") (name "Net-(Q2-B)") (class "Default")
      (node (ref "Q2") (pin "1") (pinfunction "B_1") (pintype "passive"))
      (node (ref "R39") (pin "2") (pinfunction "2_2") (pintype "passive"))
    )
    (net (code "118") (name "Net-(Q2-C)") (class "Default")
      (node (ref "Q2") (pin "3") (pinfunction "C_3") (pintype "passive"))
      (node (ref "R17") (pin "2") (pinfunction "2_2") (pintype "passive"))
      (node (ref "SG1") (pin "-") (pinfunction "2_-") (pintype "passive"))
    )
    (net (code "119") (name "Net-(Q3-G)") (class "Default")
      (node (ref "Q3") (pin "4") (pinfunction "G_4") (pintype "bidirectional"))
      (node (ref "U2") (pin "13") (pinfunction "BG_13") (pintype "bidirectional"))
    )
    (net (code "120") (name "Net-(Q4-G2)") (class "Default")
      (node (ref "Q4") (pin "4") (pinfunction "G2_4") (pintype "bidirectional"))
      (node (ref "U3") (pin "4") (pinfunction "Y_4") (pintype "bidirectional"))
    )
    (net (code "121") (name "Net-(Q5-G1)") (class "Default")
      (node (ref "C29") (pin "2") (pinfunction "2_2") (pintype "passive"))
      (node (ref "Q5") (pin "2") (pinfunction "G1_2") (pintype "bidirectional"))
      (node (ref "R2") (pin "1") (pinfunction "1_1") (pintype "passive"))
      (node (ref "ZD1") (pin "P$1") (pinfunction "A_P$1") (pintype "passive"))
    )
    (net (code "122") (name "Net-(Q5-G2)") (class "Default")
      (node (ref "Q5") (pin "4") (pinfunction "G2_4") (pintype "bidirectional"))
      (node (ref "R3") (pin "1") (pinfunction "1_1") (pintype "passive"))
      (node (ref "R31") (pin "1") (pinfunction "1_1") (pintype "passive"))
      (node (ref "ZD2") (pin "P$1") (pinfunction "A_P$1") (pintype "passive"))
    )
    (net (code "123") (name "Net-(Q5-S1)") (class "Default")
      (node (ref "C29") (pin "1") (pinfunction "1_1") (pintype "passive"))
      (node (ref "Q5") (pin "1") (pinfunction "S1_1") (pintype "bidirectional"))
      (node (ref "Q5") (pin "3") (pinfunction "S2_3") (pintype "bidirectional"))
      (node (ref "R3") (pin "2") (pinfunction "2_2") (pintype "passive"))
      (node (ref "ZD1") (pin "P$2") (pinfunction "C_P$2") (pintype "passive"))
      (node (ref "ZD2") (pin "P$2") (pinfunction "C_P$2") (pintype "passive"))
    )
    (net (code "124") (name "Net-(R31-Pad2)") (class "Default")
      (node (ref "R31") (pin "2") (pinfunction "2_2") (pintype "passive"))
      (node (ref "SW1") (pin "P$1") (pinfunction "P$1_P$1") (pintype "bidirectional"))
    )
    (net (code "125") (name "Net-(U1-CCPA)") (class "Default")
      (node (ref "C9") (pin "1") (pinfunction "1_1") (pintype "passive"))
      (node (ref "U1") (pin "P$41") (pinfunction "CCPA_P$41") (pintype "bidirectional"))
    )
    (net (code "126") (name "Net-(U1-CCPB)") (class "Default")
      (node (ref "C8") (pin "2") (pinfunction "2_2") (pintype "passive"))
      (node (ref "U1") (pin "P$19") (pinfunction "CCPB_P$19") (pintype "bidirectional"))
    )
    (net (code "127") (name "Net-(U2-BOOT)") (class "Default")
      (node (ref "C32") (pin "1") (pinfunction "1_1") (pintype "passive"))
      (node (ref "U2") (pin "11") (pinfunction "BOOT_11") (pintype "bidirectional"))
    )
    (net (code "128") (name "Net-(U2-EN{slash}SYNC)") (class "Default")
      (node (ref "R34") (pin "1") (pinfunction "1_1") (pintype "passive"))
      (node (ref "U2") (pin "3") (pinfunction "EN/SYNC_3") (pintype "bidirectional"))
    )
    (net (code "129") (name "Net-(U2-FB)") (class "Default")
      (node (ref "R32") (pin "1") (pinfunction "1_1") (pintype "passive"))
      (node (ref "R33") (pin "2") (pinfunction "2_2") (pintype "passive"))
      (node (ref "U2") (pin "1") (pinfunction "FB_1") (pintype "bidirectional"))
    )
    (net (code "130") (name "Net-(U2-VCC)") (class "Default")
      (node (ref "C33") (pin "2") (pinfunction "2_2") (pintype "passive"))
      (node (ref "U2") (pin "12") (pinfunction "VCC_12") (pintype "bidirectional"))
    )
    (net (code "131") (name "Net-(U4-CPOUT)") (class "Default")
      (node (ref "C25") (pin "1") (pinfunction "1_1") (pintype "passive"))
      (node (ref "U4") (pin "20") (pinfunction "CPOUT_20") (pintype "bidirectional"))
    )
    (net (code "132") (name "Net-(U4-REGOUT)") (class "Default")
      (node (ref "C2") (pin "1") (pinfunction "1_1") (pintype "passive"))
      (node (ref "U4") (pin "10") (pinfunction "REGOUT_10") (pintype "bidirectional"))
    )
    (net (code "133") (name "Net-(U6-IO1_1)") (class "Default")
      (node (ref "U6") (pin "P$1") (pinfunction "IO1_1_P$1") (pintype "bidirectional"))
      (node (ref "USB1") (pin "D-") (pinfunction "D-_D-") (pintype "bidirectional"))
    )
    (net (code "134") (name "Net-(U6-IO2_1)") (class "Default")
      (node (ref "U6") (pin "P$3") (pinfunction "IO2_1_P$3") (pintype "bidirectional"))
      (node (ref "USB1") (pin "D+") (pinfunction "D+_D+") (pintype "bidirectional"))
    )
    (net (code "135") (name "Net-(U7-OUTA)") (class "Default")
      (node (ref "C21") (pin "1") (pinfunction "1_1") (pintype "passive"))
      (node (ref "C23") (pin "1") (pinfunction "1_1") (pintype "passive"))
      (node (ref "U7") (pin "8") (pinfunction "OUTA_8") (pintype "bidirectional"))
      (node (ref "USB1") (pin "VBUS") (pinfunction "VBUS_VBUS") (pintype "bidirectional"))
    )
    (net (code "136") (name "Net-(U8-IO1_1)") (class "Default")
      (node (ref "U8") (pin "P$1") (pinfunction "IO1_1_P$1") (pintype "bidirectional"))
      (node (ref "USB2") (pin "D-") (pinfunction "D-_D-") (pintype "bidirectional"))
    )
    (net (code "137") (name "Net-(U8-IO2_1)") (class "Default")
      (node (ref "U8") (pin "P$3") (pinfunction "IO2_1_P$3") (pintype "bidirectional"))
      (node (ref "USB2") (pin "D+") (pinfunction "D+_D+") (pintype "bidirectional"))
    )
    (net (code "138") (name "Net-(U9-I{slash}O0)") (class "Default")
      (node (ref "LCD") (pin "DB0") (pinfunction "DB0_DB0") (pintype "bidirectional"))
      (node (ref "U9") (pin "P$5") (pinfunction "I/O0_P$5") (pintype "bidirectional"))
    )
    (net (code "139") (name "Net-(U9-I{slash}O1)") (class "Default")
      (node (ref "LCD") (pin "DB1") (pinfunction "DB1_DB1") (pintype "bidirectional"))
      (node (ref "U9") (pin "P$6") (pinfunction "I/O1_P$6") (pintype "bidirectional"))
    )
    (net (code "140") (name "Net-(U9-I{slash}O2)") (class "Default")
      (node (ref "LCD") (pin "DB2") (pinfunction "DB2_DB2") (pintype "bidirectional"))
      (node (ref "U9") (pin "P$9") (pinfunction "I/O2_P$9") (pintype "bidirectional"))
    )
    (net (code "141") (name "Net-(U9-I{slash}O3)") (class "Default")
      (node (ref "LCD") (pin "DB3") (pinfunction "DB3_DB3") (pintype "bidirectional"))
      (node (ref "U9") (pin "P$10") (pinfunction "I/O3_P$10") (pintype "bidirectional"))
    )
    (net (code "142") (name "Net-(U9-I{slash}O4)") (class "Default")
      (node (ref "LCD") (pin "DB4") (pinfunction "DB4_DB4") (pintype "bidirectional"))
      (node (ref "U9") (pin "P$15") (pinfunction "I/O4_P$15") (pintype "bidirectional"))
    )
    (net (code "143") (name "Net-(U9-I{slash}O5)") (class "Default")
      (node (ref "LCD") (pin "DB5") (pinfunction "DB5_DB5") (pintype "bidirectional"))
      (node (ref "U9") (pin "P$16") (pinfunction "I/O5_P$16") (pintype "bidirectional"))
    )
    (net (code "144") (name "Net-(U9-I{slash}O6)") (class "Default")
      (node (ref "LCD") (pin "DB6") (pinfunction "DB6_DB6") (pintype "bidirectional"))
      (node (ref "U9") (pin "P$19") (pinfunction "I/O6_P$19") (pintype "bidirectional"))
    )
    (net (code "145") (name "Net-(U9-I{slash}O7)") (class "Default")
      (node (ref "LCD") (pin "DB7") (pinfunction "DB7_DB7") (pintype "bidirectional"))
      (node (ref "U9") (pin "P$20") (pinfunction "I/O7_P$20") (pintype "bidirectional"))
    )
    (net (code "146") (name "Net-(U9-NRESET)") (class "Default")
      (node (ref "R16") (pin "1") (pinfunction "1_1") (pintype "passive"))
      (node (ref "U9") (pin "P$1") (pinfunction "NRESET_P$1") (pintype "bidirectional"))
    )
    (net (code "147") (name "Net-(XB1-PWM0{slash}RSSI)") (class "Default")
      (node (ref "LED5") (pin "A") (pinfunction "A_A") (pintype "passive"))
      (node (ref "XB1") (pin "6") (pinfunction "PWM0/RSSI_6") (pintype "output"))
    )
    (net (code "148") (name "unconnected-(J6-Pad1)") (class "Default")
      (node (ref "J6") (pin "1") (pinfunction "1_1") (pintype "passive"))
    )
    (net (code "149") (name "unconnected-(J6-Pad6)") (class "Default")
      (node (ref "J6") (pin "6") (pinfunction "6_6") (pintype "passive"))
    )
    (net (code "150") (name "unconnected-(SD-SHIELD-PadCD1)") (class "Default")
      (node (ref "SD") (pin "CD1") (pinfunction "SHIELD_CD1") (pintype "bidirectional"))
    )
    (net (code "151") (name "unconnected-(SD-SHIELD-PadCD2)") (class "Default")
      (node (ref "SD") (pin "CD2") (pinfunction "SHIELD_CD2") (pintype "bidirectional"))
    )
    (net (code "152") (name "unconnected-(U2-PGOOD-Pad2)") (class "Default")
      (node (ref "U2") (pin "2") (pinfunction "PGOOD_2") (pintype "bidirectional"))
    )
    (net (code "153") (name "unconnected-(U3-NC-Pad1)") (class "Default")
      (node (ref "U3") (pin "1") (pinfunction "NC_1") (pintype "bidirectional"))
    )
    (net (code "154") (name "unconnected-(U4-AUX_CL-Pad7)") (class "Default")
      (node (ref "U4") (pin "7") (pinfunction "AUX_CL_7") (pintype "bidirectional"))
    )
    (net (code "155") (name "unconnected-(U4-AUX_DA-Pad6)") (class "Default")
      (node (ref "U4") (pin "6") (pinfunction "AUX_DA_6") (pintype "bidirectional"))
    )
    (net (code "156") (name "unconnected-(U4-INT-Pad12)") (class "Default")
      (node (ref "U4") (pin "12") (pinfunction "INT_12") (pintype "bidirectional"))
    )
    (net (code "157") (name "unconnected-(U9-NINT-PadP$11)") (class "Default")
      (node (ref "U9") (pin "P$11") (pinfunction "NINT_P$11") (pintype "bidirectional"))
    )
    (net (code "158") (name "unconnected-(XB1-AD0{slash}DIO0-Pad20)") (class "Default")
      (node (ref "XB1") (pin "20") (pinfunction "AD0/DIO0_20") (pintype "bidirectional"))
    )
    (net (code "159") (name "unconnected-(XB1-AD1{slash}DIO1-Pad19)") (class "Default")
      (node (ref "XB1") (pin "19") (pinfunction "AD1/DIO1_19") (pintype "bidirectional"))
    )
    (net (code "160") (name "unconnected-(XB1-AD2{slash}DIO2-Pad18)") (class "Default")
      (node (ref "XB1") (pin "18") (pinfunction "AD2/DIO2_18") (pintype "bidirectional"))
    )
    (net (code "161") (name "unconnected-(XB1-ASSOC{slash}AD5{slash}DIO5-Pad15)") (class "Default")
      (node (ref "XB1") (pin "15") (pinfunction "ASSOC/AD5/DIO5_15") (pintype "bidirectional"))
    )
    (net (code "162") (name "unconnected-(XB1-CD{slash}DOUT_EN{slash}DO8-Pad4)") (class "Default")
      (node (ref "XB1") (pin "4") (pinfunction "CD/DOUT_EN/DO8_4") (pintype "output"))
    )
    (net (code "163") (name "unconnected-(XB1-COORD_SEL{slash}AD3{slash}DIO3-Pad17)") (class "Default")
      (node (ref "XB1") (pin "17") (pinfunction "COORD_SEL/AD3/DIO3_17") (pintype "bidirectional"))
    )
    (net (code "164") (name "unconnected-(XB1-ON{slash}~{SLEEP}-Pad13)") (class "Default")
      (node (ref "XB1") (pin "13") (pinfunction "ON/~{SLEEP}_13") (pintype "output"))
    )
    (net (code "165") (name "unconnected-(XB1-RF_TX{slash}AD4{slash}DIO4-Pad11)") (class "Default")
      (node (ref "XB1") (pin "11") (pinfunction "RF_TX/AD4/DIO4_11") (pintype "bidirectional"))
    )
    (net (code "166") (name "unconnected-(XB1-VREF-Pad14)") (class "Default")
      (node (ref "XB1") (pin "14") (pinfunction "VREF_14") (pintype "input"))
    )
    (net (code "167") (name "unconnected-(XB1-~{CTS}{slash}DIO7-Pad12)") (class "Default")
      (node (ref "XB1") (pin "12") (pinfunction "~{CTS}/DIO7_12") (pintype "bidirectional"))
    )
    (net (code "168") (name "unconnected-(XB1-~{DTR}{slash}SLEEP_RQ{slash}DI8-Pad9)") (class "Default")
      (node (ref "XB1") (pin "9") (pinfunction "~{DTR}/SLEEP_RQ/DI8_9") (pintype "bidirectional"))
    )
    (net (code "169") (name "unconnected-(XB1-~{RESET}-Pad5)") (class "Default")
      (node (ref "XB1") (pin "5") (pinfunction "~{RESET}_5") (pintype "input"))
    )
    (net (code "170") (name "unconnected-(XB1-~{RTS}{slash}AD6{slash}DIO6-Pad16)") (class "Default")
      (node (ref "XB1") (pin "16") (pinfunction "~{RTS}/AD6/DIO6_16") (pintype "bidirectional"))
    )
  )
)
